# ProDoc_TeenAstro_Redux_v2_6_5M_2025-03-2.net
KiCad netlist of a schematic drawn in EasyEDA Pro
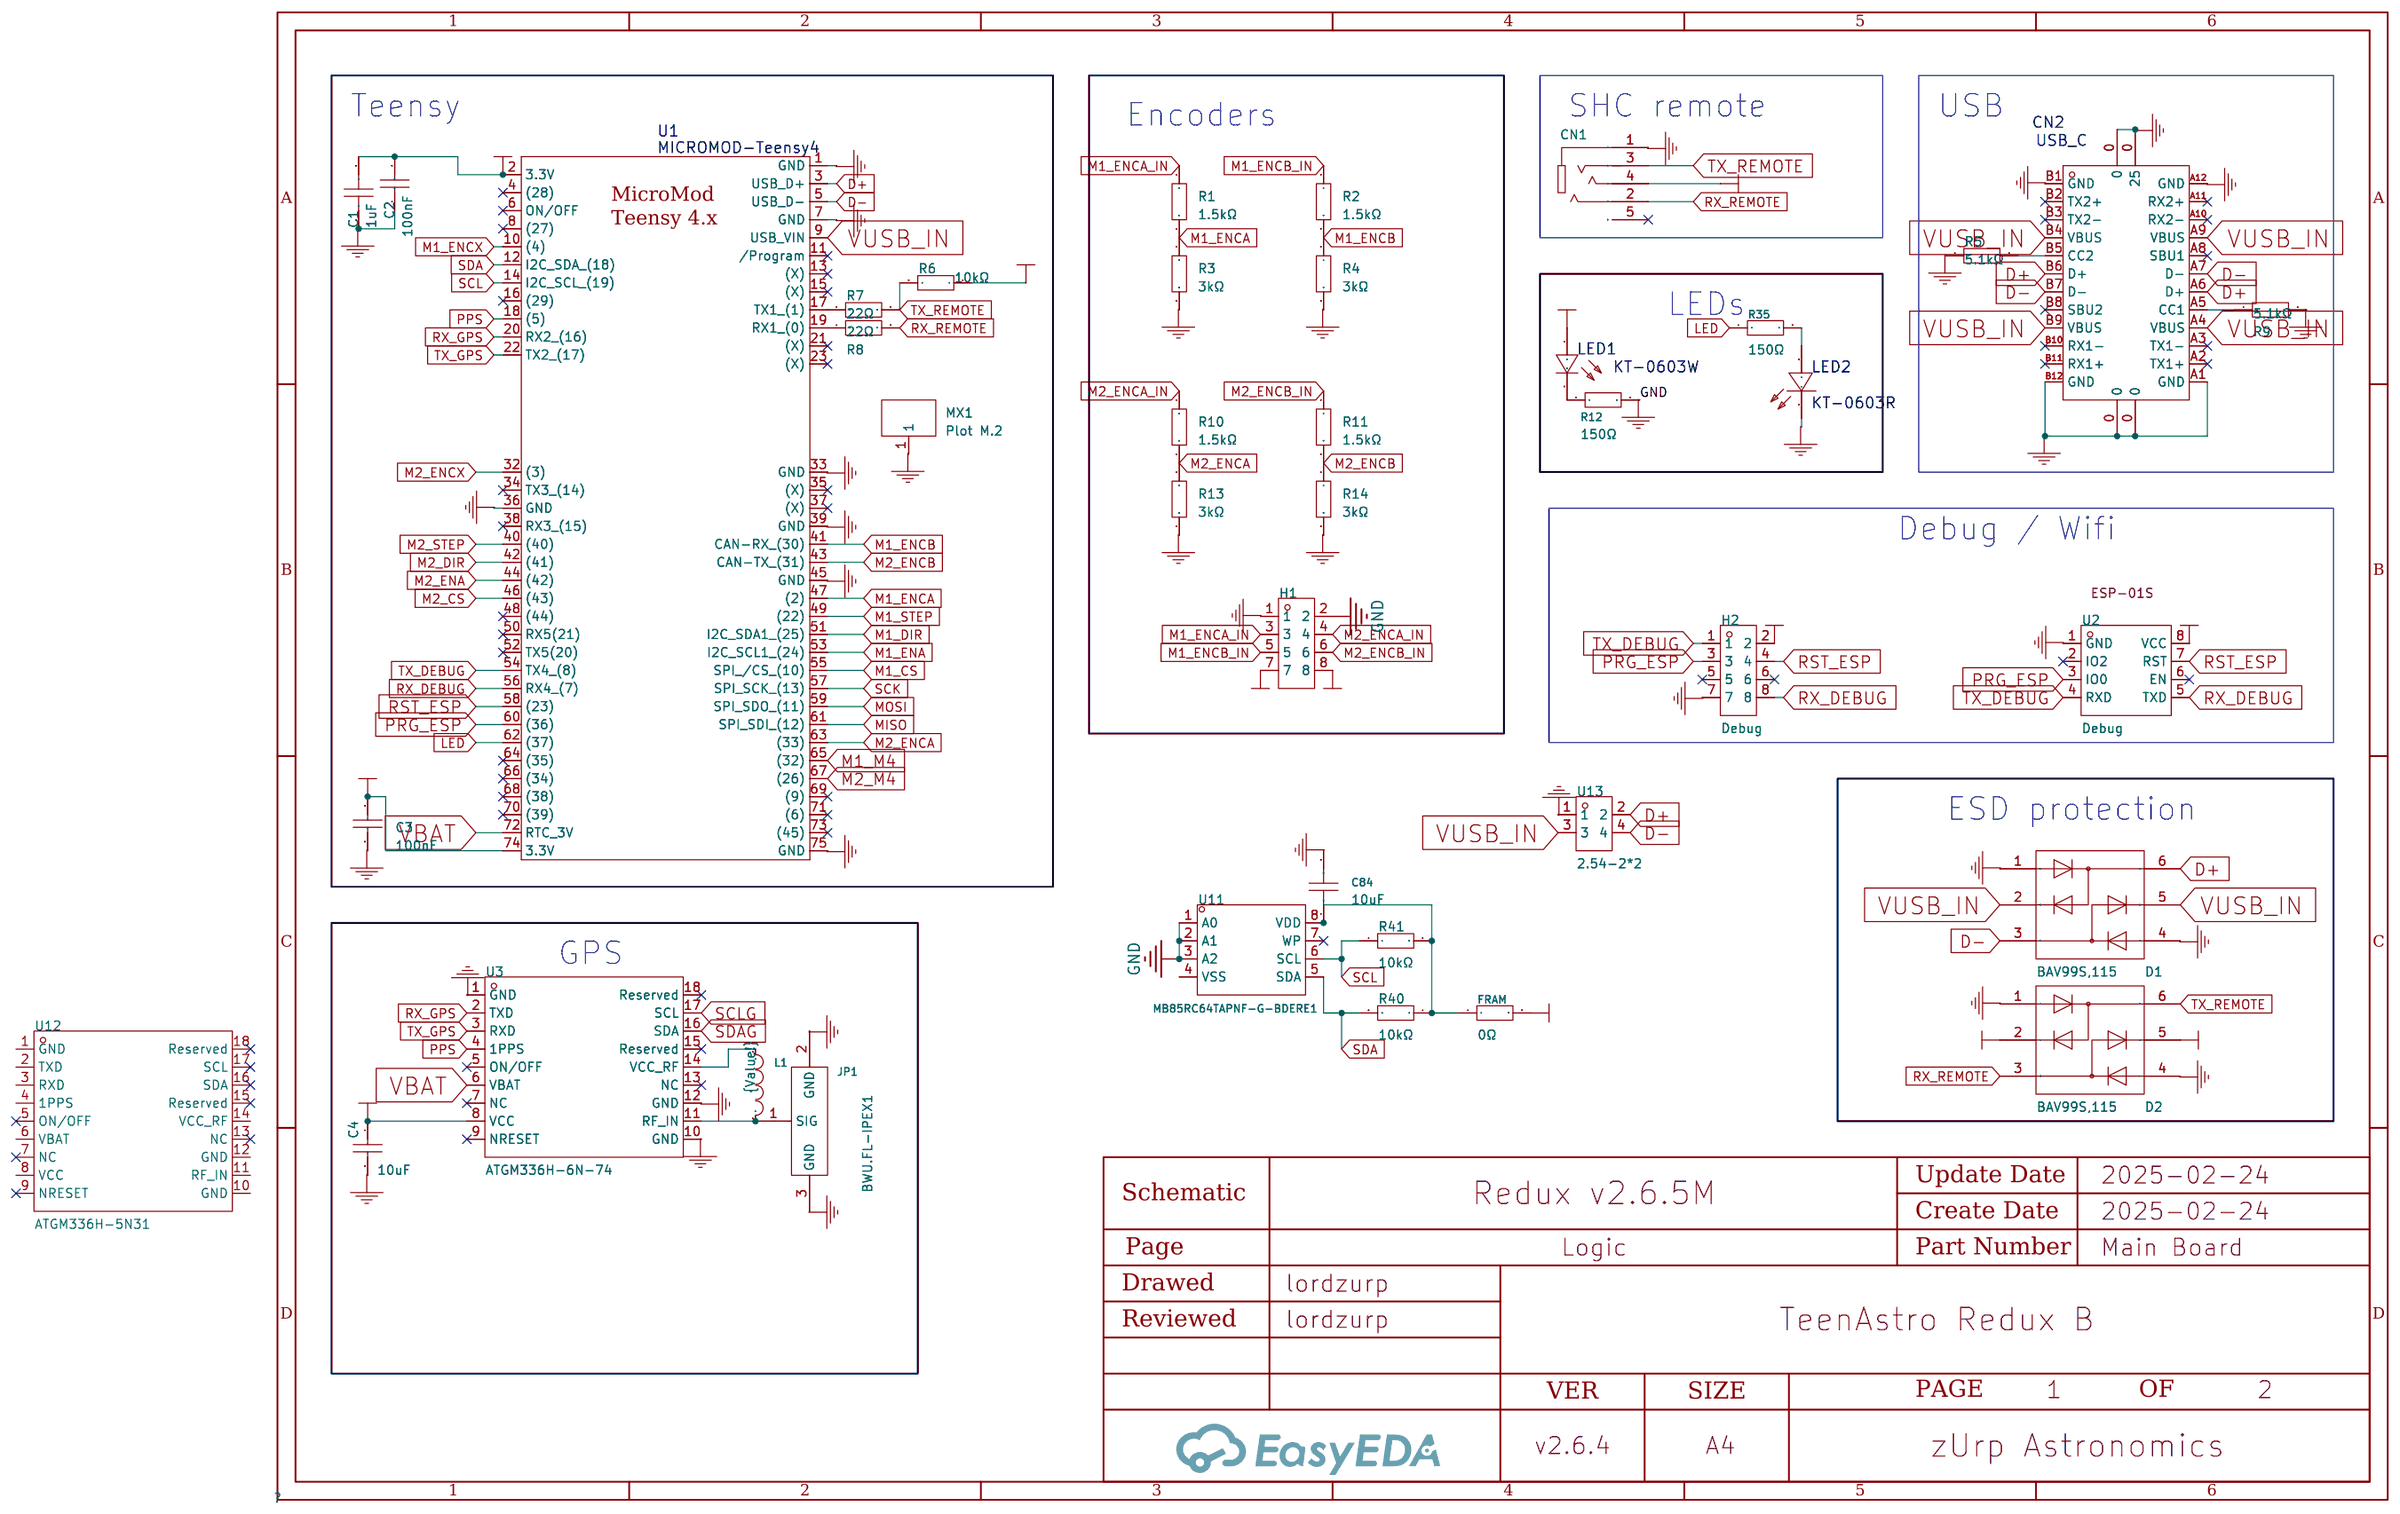
[diagram p0: Logic]
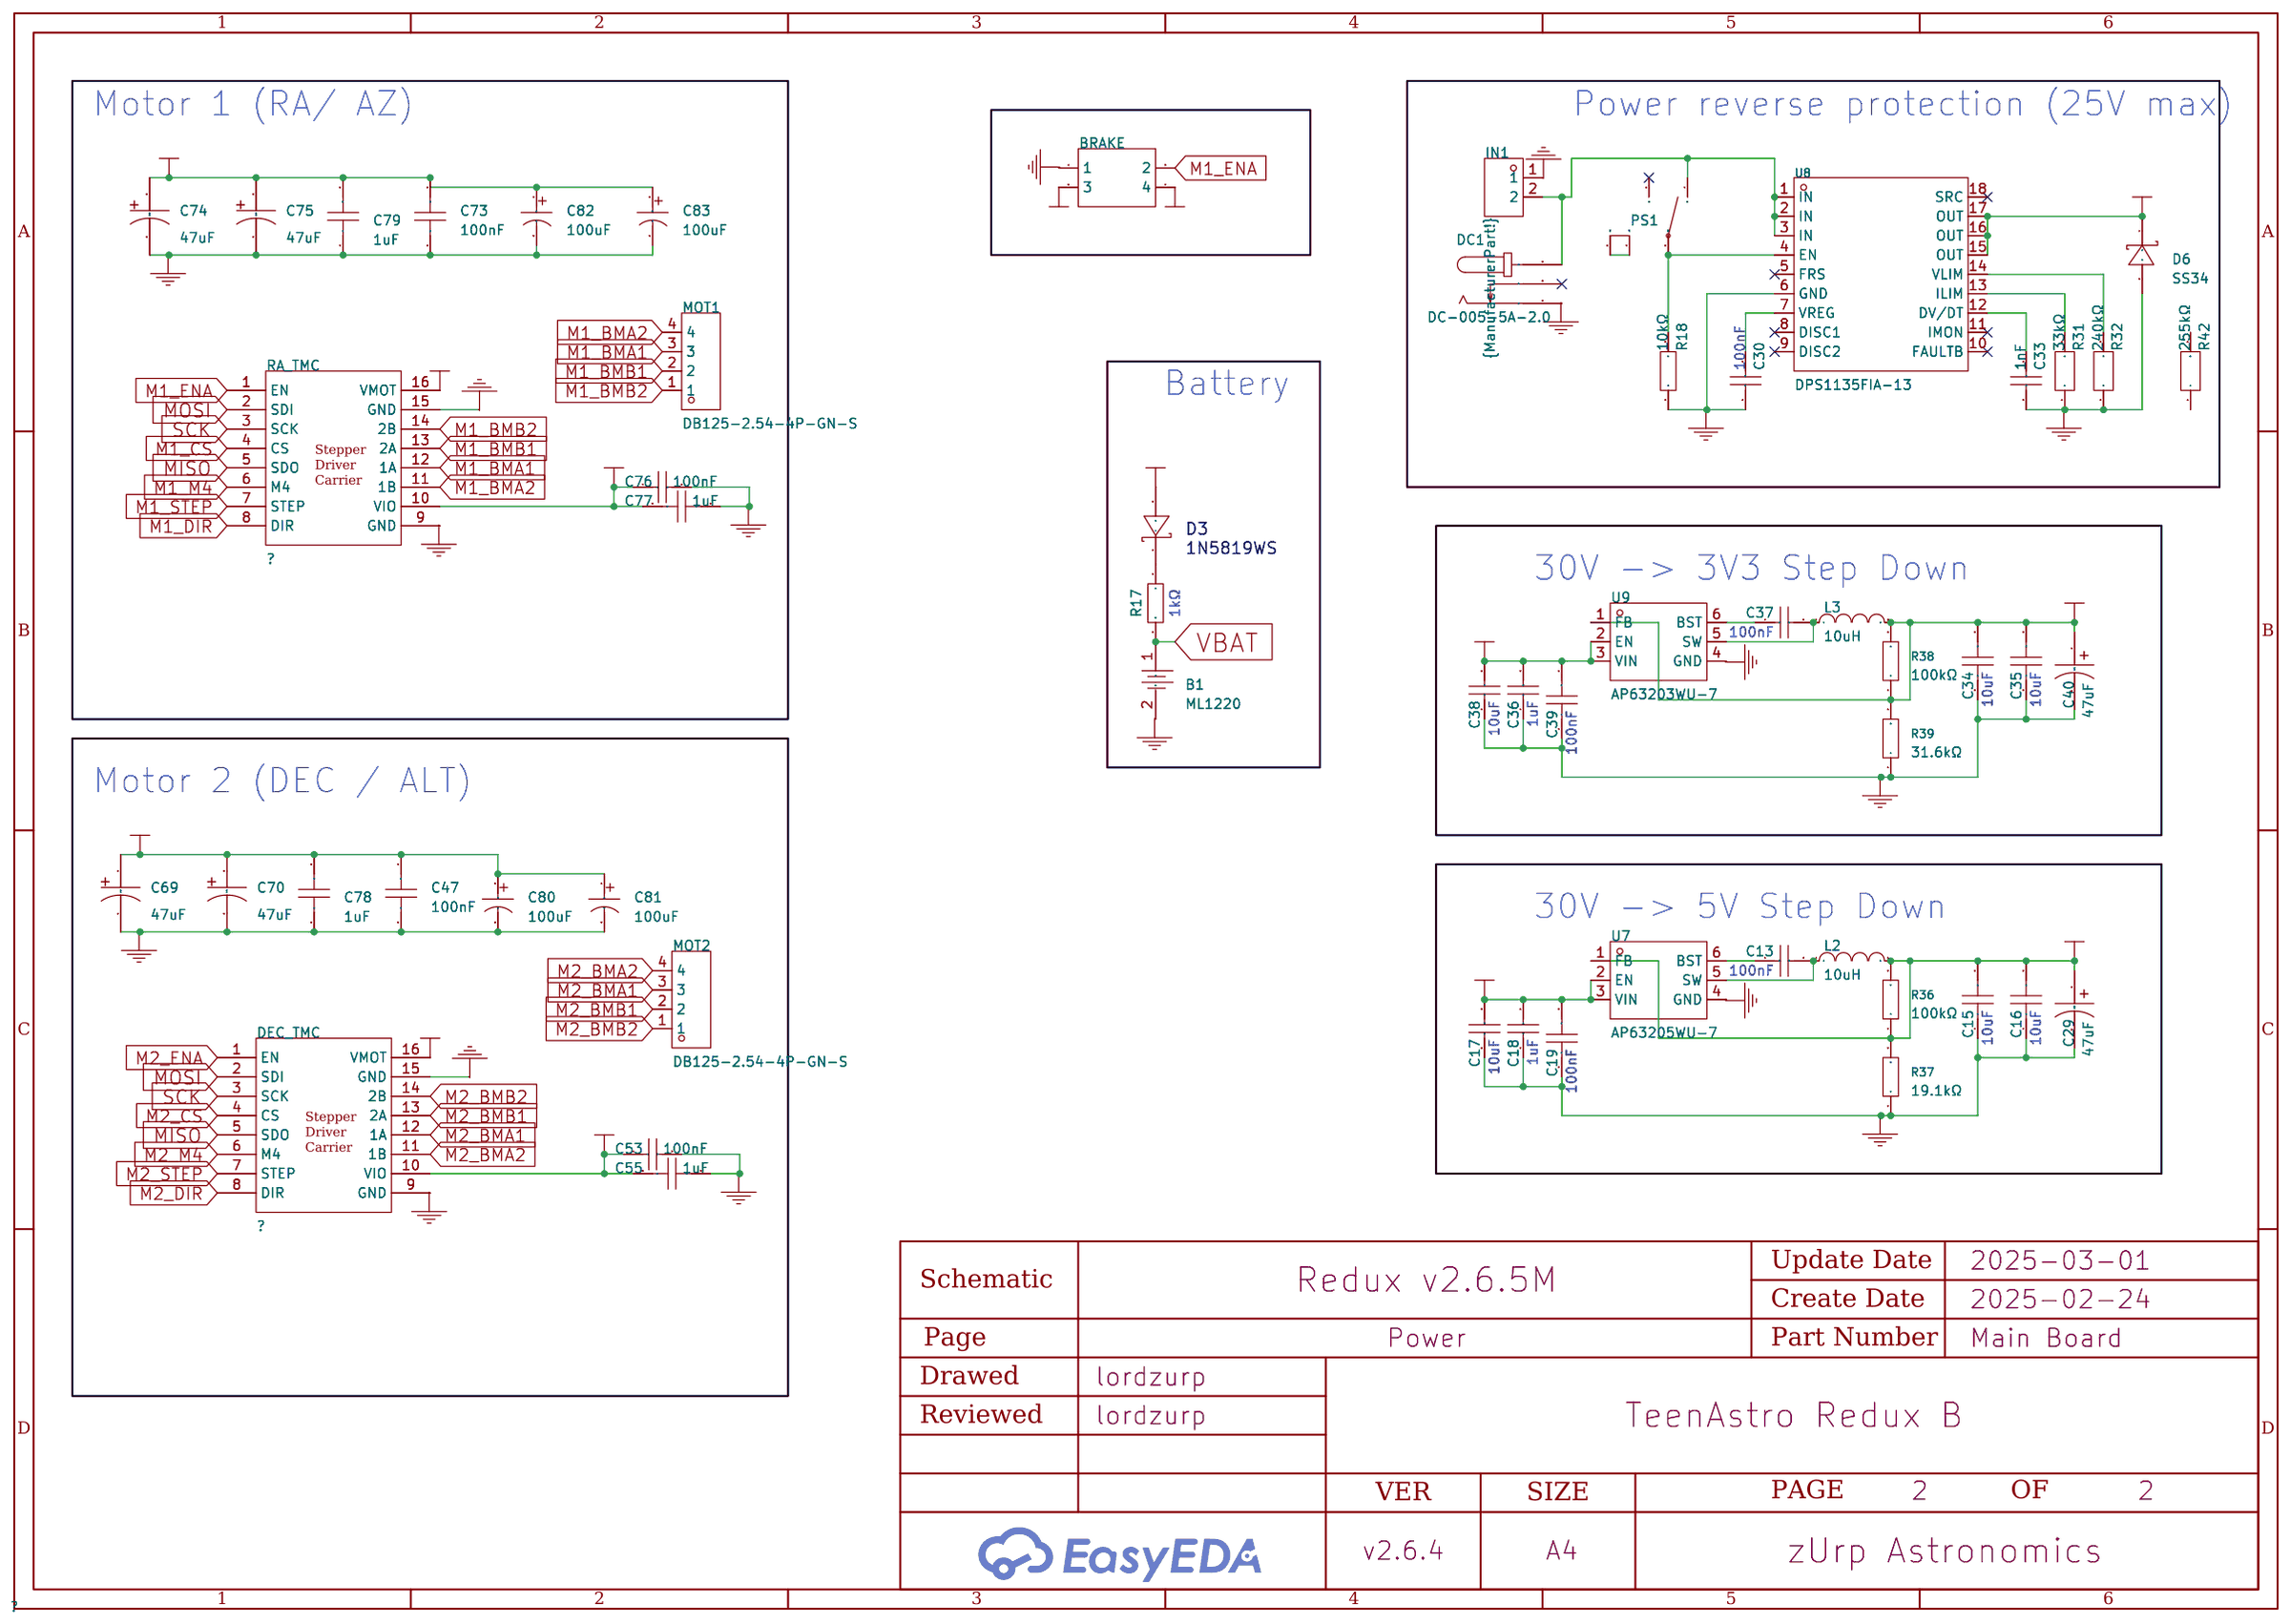
[diagram p1: Power]

(export (version "E")
  (design (tool "Eeschema 10.0.6"))
  (components
    (comp (ref "C1")
      (value "1uF")
      (footprint "easyedapro:C0402")
      (fields
        (field (name "Manufacturer Part") "CL05A105KA5NQNC")
        (field (name "Manufacturer") "SAMSUNG(三星)")
      )
      (libsource (lib "easyedapro") (part "CL05A105KA5NQNC"))
    )
    (comp (ref "C2")
      (value "100nF")
      (footprint "easyedapro:C0402")
      (fields
        (field (name "Manufacturer Part") "CL05B104KO5NNNC")
        (field (name "Manufacturer") "SAMSUNG(三星)")
      )
      (libsource (lib "easyedapro") (part "CL05B104KO5NNNC"))
    )
    (comp (ref "C3")
      (value "100nF")
      (footprint "easyedapro:C0402")
      (fields
        (field (name "Manufacturer Part") "CL05B104KO5NNNC")
        (field (name "Manufacturer") "SAMSUNG(三星)")
      )
      (libsource (lib "easyedapro") (part "CL05B104KO5NNNC"))
    )
    (comp (ref "C4")
      (value "10uF")
      (footprint "easyedapro:C1206")
      (fields
        (field (name "Manufacturer Part") "CL31A106KBHNNNE")
        (field (name "Manufacturer") "SAMSUNG(三星)")
      )
      (libsource (lib "easyedapro") (part "CL31A106KBHNNNE"))
    )
    (comp (ref "C84")
      (value "10uF")
      (footprint "easyedapro:C0603")
      (fields
        (field (name "Manufacturer Part") "CL10A106KP8NNNC")
        (field (name "Manufacturer") "SAMSUNG(三星)")
      )
      (libsource (lib "easyedapro") (part "CL10A106KP8NNNC"))
    )
    (comp (ref "CN1")
      (value "PJ-327E-SMT")
      (footprint "easyedapro:AUDIO-SMD_PJ-327E-SMT")
      (fields (field (name "Manufacturer") "XKBConnectivity(中国星坤)"))
      (libsource (lib "easyedapro") (part "PJ-327E-SMT"))
    )
    (comp (ref "CN2")
      (value "USB_C")
      (footprint "easyedapro:USB-C-SMD_TYPE-C-USB-18")
      (fields (field (name "Manufacturer Part") "105450-0101") (field (name "Manufacturer") "MOLEX"))
      (libsource (lib "easyedapro") (part "USB_C"))
    )
    (comp (ref "D1")
      (value "BAV99S,115")
      (footprint "easyedapro:SOT-363_L2.0-W1.3-P0.65-LS2.1-TL")
      (fields (field (name "Manufacturer") "Nexperia(安世)"))
      (libsource (lib "easyedapro") (part "BAV99S,135"))
    )
    (comp (ref "D2")
      (value "BAV99S,115")
      (footprint "easyedapro:SOT-363_L2.0-W1.3-P0.65-LS2.1-TL")
      (fields (field (name "Manufacturer") "Nexperia(安世)"))
      (libsource (lib "easyedapro") (part "BAV99S,135"))
    )
    (comp (ref "FRAM")
      (value "0Ω")
      (footprint "easyedapro:R0402")
      (fields
        (field (name "Manufacturer Part") "0402WGF0000TCE")
        (field (name "Manufacturer") "UNI-ROYAL(厚声)")
      )
      (libsource (lib "easyedapro") (part "0402WGF0000TCE"))
    )
    (comp (ref "H1")
      (value "DW127R-22-08-34")
      (fields (field (name "Manufacturer") "DEALON(德艺隆)"))
      (libsource (lib "easyedapro") (part "DZ254R-22-08-63"))
    )
    (comp (ref "H2")
      (value "Debug")
      (fields (field (name "Manufacturer Part") "DS1023-2*4SF11") (field (name "Manufacturer") "CONNFLY"))
      (libsource (lib "easyedapro") (part "DZ254R-22-08-63"))
    )
    (comp (ref "JP1")
      (value "BWU.FL-IPEX1")
      (fields (field (name "Manufacturer") "BAT WIRELESS(蝙蝠无线)"))
      (libsource (lib "easyedapro") (part "U.FL-R-SMT-1(80)"))
    )
    (comp (ref "L1")
      (value "{Value!}")
      (footprint "easyedapro:IND-SMD_L1.6-W0.8-1")
      (fields (field (name "Manufacturer Part") "LQW18AN47NJ00D") (field (name "Manufacturer") "muRata(村田)"))
      (libsource (lib "easyedapro") (part "LQW18AN47NJ00D"))
    )
    (comp (ref "LED1")
      (value "KT-0603W")
      (description "Emitted Color:White")
      (fields (field (name "Manufacturer") "KENTO"))
      (libsource (lib "easyedapro") (part "power"))
    )
    (comp (ref "LED2")
      (value "KT-0603R")
      (footprint "easyedapro:LED0603-RD")
      (fields (field (name "Manufacturer") "KENTO"))
      (libsource (lib "easyedapro") (part "KT-0603R"))
    )
    (comp (ref "MX1")
      (value "Plot M.2")
      (footprint "easyedapro:SMD_BD5.6-D4.1")
      (fields (field (name "Manufacturer Part") "SMTSO3030CTJ") (field (name "Manufacturer") "Sinhoo(雄和远景)"))
      (libsource (lib "easyedapro") (part "SMTSO3030CTJ"))
    )
    (comp (ref "R1")
      (value "1.5kΩ")
      (footprint "easyedapro:R0603")
      (fields
        (field (name "Manufacturer Part") "0603WAF1501T5E")
        (field (name "Manufacturer") "UNI-ROYAL(厚声)")
      )
      (libsource (lib "easyedapro") (part "0603WAF1501T5E"))
    )
    (comp (ref "R2")
      (value "1.5kΩ")
      (footprint "easyedapro:R0603")
      (fields
        (field (name "Manufacturer Part") "0603WAF1501T5E")
        (field (name "Manufacturer") "UNI-ROYAL(厚声)")
      )
      (libsource (lib "easyedapro") (part "0603WAF1501T5E"))
    )
    (comp (ref "R3")
      (value "3kΩ")
      (footprint "easyedapro:R0603")
      (fields
        (field (name "Manufacturer Part") "0603WAF3001T5E")
        (field (name "Manufacturer") "UNI-ROYAL(厚声)")
      )
      (libsource (lib "easyedapro") (part "0603WAF3001T5E"))
    )
    (comp (ref "R4")
      (value "3kΩ")
      (footprint "easyedapro:R0603")
      (fields
        (field (name "Manufacturer Part") "0603WAF3001T5E")
        (field (name "Manufacturer") "UNI-ROYAL(厚声)")
      )
      (libsource (lib "easyedapro") (part "0603WAF3001T5E"))
    )
    (comp (ref "R5")
      (value "5.1kΩ")
      (fields
        (field (name "Manufacturer Part") "0603WAF5101T5E")
        (field (name "Manufacturer") "UNI-ROYAL(厚声)")
      )
      (libsource (lib "easyedapro") (part "RC0603JR-075K1L"))
    )
    (comp (ref "R6")
      (value "10kΩ")
      (footprint "easyedapro:R0402")
      (fields
        (field (name "Manufacturer Part") "0402WGF1002TCE")
        (field (name "Manufacturer") "UNI-ROYAL(厚声)")
      )
      (libsource (lib "easyedapro") (part "0402WGF1002TCE"))
    )
    (comp (ref "R7")
      (value "22Ω")
      (footprint "easyedapro:R0402")
      (fields
        (field (name "Manufacturer Part") "0402WGF220JTCE")
        (field (name "Manufacturer") "UNI-ROYAL(厚声)")
      )
      (libsource (lib "easyedapro") (part "0402WGF220JTCE"))
    )
    (comp (ref "R8")
      (value "22Ω")
      (footprint "easyedapro:R0402")
      (fields
        (field (name "Manufacturer Part") "0402WGF220JTCE")
        (field (name "Manufacturer") "UNI-ROYAL(厚声)")
      )
      (libsource (lib "easyedapro") (part "0402WGF220JTCE"))
    )
    (comp (ref "R9")
      (value "5.1kΩ")
      (fields
        (field (name "Manufacturer Part") "0603WAF5101T5E")
        (field (name "Manufacturer") "UNI-ROYAL(厚声)")
      )
      (libsource (lib "easyedapro") (part "RC0603JR-075K1L"))
    )
    (comp (ref "R10")
      (value "1.5kΩ")
      (footprint "easyedapro:R0603")
      (fields
        (field (name "Manufacturer Part") "0603WAF1501T5E")
        (field (name "Manufacturer") "UNI-ROYAL(厚声)")
      )
      (libsource (lib "easyedapro") (part "0603WAF1501T5E"))
    )
    (comp (ref "R11")
      (value "1.5kΩ")
      (footprint "easyedapro:R0603")
      (fields
        (field (name "Manufacturer Part") "0603WAF1501T5E")
        (field (name "Manufacturer") "UNI-ROYAL(厚声)")
      )
      (libsource (lib "easyedapro") (part "0603WAF1501T5E"))
    )
    (comp (ref "R12") (value "150Ω") (libsource (lib "easyedapro") (part "0603WAF1001T5E")))
    (comp (ref "R13")
      (value "3kΩ")
      (footprint "easyedapro:R0603")
      (fields
        (field (name "Manufacturer Part") "0603WAF3001T5E")
        (field (name "Manufacturer") "UNI-ROYAL(厚声)")
      )
      (libsource (lib "easyedapro") (part "0603WAF3001T5E"))
    )
    (comp (ref "R14")
      (value "3kΩ")
      (footprint "easyedapro:R0603")
      (fields
        (field (name "Manufacturer Part") "0603WAF3001T5E")
        (field (name "Manufacturer") "UNI-ROYAL(厚声)")
      )
      (libsource (lib "easyedapro") (part "0603WAF3001T5E"))
    )
    (comp (ref "R35")
      (value "150Ω")
      (footprint "easyedapro:R0603")
      (fields
        (field (name "Manufacturer Part") "0603WAF1500T5E")
        (field (name "Manufacturer") "UNI-ROYAL(厚声)")
      )
      (libsource (lib "easyedapro") (part "0603WAF1500T5E"))
    )
    (comp (ref "R40")
      (value "10kΩ")
      (footprint "easyedapro:R0402")
      (fields
        (field (name "Manufacturer Part") "0402WGF1002TCE")
        (field (name "Manufacturer") "UNI-ROYAL(厚声)")
      )
      (libsource (lib "easyedapro") (part "0402WGF1002TCE"))
    )
    (comp (ref "R41")
      (value "10kΩ")
      (footprint "easyedapro:R0402")
      (fields
        (field (name "Manufacturer Part") "0402WGF1002TCE")
        (field (name "Manufacturer") "UNI-ROYAL(厚声)")
      )
      (libsource (lib "easyedapro") (part "0402WGF1002TCE"))
    )
    (comp (ref "U1")
      (value "MICROMOD-Teensy4")
      (footprint "easyedapro:M.2-CONNECTOR-E")
      (fields (field (name "Manufacturer") "Foxconn") (field (name "Manufacturer Part") "AS0BC21-S48BE-7H"))
      (libsource (lib "easyedapro") (part "MICROMOD-Teensy4"))
    )
    (comp (ref "U2")
      (value "2.4GHz")
      (footprint "easyedapro:WIFIM-TH_8P-L24.7-W14.4-P2.54")
      (fields (field (name "Manufacturer Part") "ESP-01S") (field (name "Manufacturer") "Ai-Thinker(安信可)"))
      (libsource (lib "easyedapro") (part "ESP-01"))
    )
    (comp (ref "U3")
      (value "ATGM336H-6N-74")
      (footprint "easyedapro:GPSM-SMD_ATGM336H-TR")
      (fields (field (name "Manufacturer") "杭州中科微"))
      (libsource (lib "easyedapro") (part "ATGM336H-5N31"))
    )
    (comp (ref "U11")
      (value "MB85RC64TAPNF-G-BDERE1")
      (footprint "easyedapro:SOP-8_L5.0-W4.0-P1.27-LS6.0-BL")
      (fields (field (name "Manufacturer") "RAMXEED/FUJITSU(富士通)"))
      (libsource (lib "easyedapro") (part "MB85RC64TAPNF-G-BDERE1"))
    )
    (comp (ref "U12")
      (value "ATGM336H-5N31")
      (footprint "easyedapro:GPSM-SMD_ATGM336H-TR")
      (fields (field (name "Manufacturer") "杭州中科微"))
      (libsource (lib "easyedapro") (part "ATGM336H-5N31"))
    )
    (comp (ref "U13")
      (value "2.54-2*2")
      (footprint "easyedapro:HDR-TH_4P-P2.54-V-F-R2-C2-S2.54")
      (fields (field (name "Manufacturer") "ZHOURI(洲日)"))
      (libsource (lib "easyedapro") (part "2.54-2*2"))
    )
    (comp (ref "B1")
      (value "ML1220")
      (footprint "easyedapro:BAT-SMD_CR1220-2")
      (fields (field (name "Manufacturer Part") "CR1220-2") (field (name "Manufacturer") "Q&J"))
      (libsource (lib "easyedapro") (part "CR1220-2"))
    )
    (comp (ref "BRAKE")
      (value "X4621WVS-2x02I-C40D64")
      (fields (field (name "Manufacturer") "XKB Connection(中国星坤)"))
      (libsource (lib "easyedapro") (part "Header-Male-2.54_2x2"))
    )
    (comp (ref "C13")
      (value "100nF")
      (footprint "easyedapro:C0402")
      (fields
        (field (name "Manufacturer Part") "CL05B104KO5NNNC")
        (field (name "Manufacturer") "SAMSUNG(三星)")
      )
      (libsource (lib "easyedapro") (part "CL05B104KO5NNNC"))
    )
    (comp (ref "C15")
      (value "10uF")
      (fields
        (field (name "Manufacturer Part") "CL21A106KAYNNNE")
        (field (name "Manufacturer") "SAMSUNG(三星)")
      )
      (libsource (lib "easyedapro") (part "C3225X5R1E226MT000E"))
    )
    (comp (ref "C16")
      (value "10uF")
      (fields
        (field (name "Manufacturer Part") "CL21A106KAYNNNE")
        (field (name "Manufacturer") "SAMSUNG(三星)")
      )
      (libsource (lib "easyedapro") (part "C3225X5R1E226MT000E"))
    )
    (comp (ref "C17")
      (value "10uF")
      (footprint "easyedapro:C1206")
      (fields
        (field (name "Manufacturer Part") "CL31A106KBHNNNE")
        (field (name "Manufacturer") "SAMSUNG(三星)")
      )
      (libsource (lib "easyedapro") (part "CL31A106KBHNNNE"))
    )
    (comp (ref "C18")
      (value "1uF")
      (footprint "easyedapro:C0805")
      (fields
        (field (name "Manufacturer Part") "CL21B105KBFNNNE")
        (field (name "Manufacturer") "SAMSUNG(三星)")
      )
      (libsource (lib "easyedapro") (part "CL21B105KBFNNNE"))
    )
    (comp (ref "C19")
      (value "100nF")
      (footprint "easyedapro:C0603")
      (fields
        (field (name "Manufacturer Part") "CC0603KRX7R9BB104")
        (field (name "Manufacturer") "YAGEO(国巨)")
      )
      (libsource (lib "easyedapro") (part "CC0603KRX7R9BB104"))
    )
    (comp (ref "C29")
      (value "47uF")
      (fields
        (field (name "Manufacturer Part") "CA45-A-10V-47uF-M")
        (field (name "Manufacturer") "CEC(振华新云)")
      )
      (libsource (lib "easyedapro") (part "F930J476MAA_C471392"))
    )
    (comp (ref "C30")
      (value "100nF")
      (footprint "easyedapro:C0402")
      (fields
        (field (name "Manufacturer Part") "CL05B104KO5NNNC")
        (field (name "Manufacturer") "SAMSUNG(三星)")
      )
      (libsource (lib "easyedapro") (part "CL05B104KO5NNNC"))
    )
    (comp (ref "C33")
      (value "1nF")
      (footprint "easyedapro:C0402")
      (fields (field (name "Manufacturer Part") "0402B102K500NT") (field (name "Manufacturer") "FH(风华)"))
      (libsource (lib "easyedapro") (part "0402B102K500NT"))
    )
    (comp (ref "C34")
      (value "10uF")
      (fields
        (field (name "Manufacturer Part") "CL21A106KAYNNNE")
        (field (name "Manufacturer") "SAMSUNG(三星)")
      )
      (libsource (lib "easyedapro") (part "C3225X5R1E226MT000E"))
    )
    (comp (ref "C35")
      (value "10uF")
      (fields
        (field (name "Manufacturer Part") "CL21A106KAYNNNE")
        (field (name "Manufacturer") "SAMSUNG(三星)")
      )
      (libsource (lib "easyedapro") (part "C3225X5R1E226MT000E"))
    )
    (comp (ref "C36")
      (value "1uF")
      (footprint "easyedapro:C0805")
      (fields
        (field (name "Manufacturer Part") "CL21B105KBFNNNE")
        (field (name "Manufacturer") "SAMSUNG(三星)")
      )
      (libsource (lib "easyedapro") (part "CL21B105KBFNNNE"))
    )
    (comp (ref "C37")
      (value "100nF")
      (footprint "easyedapro:C0402")
      (fields
        (field (name "Manufacturer Part") "CL05B104KO5NNNC")
        (field (name "Manufacturer") "SAMSUNG(三星)")
      )
      (libsource (lib "easyedapro") (part "CL05B104KO5NNNC"))
    )
    (comp (ref "C38")
      (value "10uF")
      (footprint "easyedapro:C1206")
      (fields
        (field (name "Manufacturer Part") "CL31A106KBHNNNE")
        (field (name "Manufacturer") "SAMSUNG(三星)")
      )
      (libsource (lib "easyedapro") (part "CL31A106KBHNNNE"))
    )
    (comp (ref "C39")
      (value "100nF")
      (footprint "easyedapro:C0603")
      (fields
        (field (name "Manufacturer Part") "CC0603KRX7R9BB104")
        (field (name "Manufacturer") "YAGEO(国巨)")
      )
      (libsource (lib "easyedapro") (part "CC0603KRX7R9BB104"))
    )
    (comp (ref "C40")
      (value "47uF")
      (fields
        (field (name "Manufacturer Part") "CA45-A-10V-47uF-M")
        (field (name "Manufacturer") "CEC(振华新云)")
      )
      (libsource (lib "easyedapro") (part "F930J476MAA_C471392"))
    )
    (comp (ref "C47")
      (value "100nF")
      (footprint "easyedapro:C0603")
      (fields
        (field (name "Manufacturer Part") "CC0603KRX7R9BB104")
        (field (name "Manufacturer") "YAGEO(国巨)")
      )
      (libsource (lib "easyedapro") (part "CC0603KRX7R9BB104"))
    )
    (comp (ref "C53")
      (value "100nF")
      (footprint "easyedapro:C0402")
      (fields
        (field (name "Manufacturer Part") "CL05B104KO5NNNC")
        (field (name "Manufacturer") "SAMSUNG(三星)")
      )
      (libsource (lib "easyedapro") (part "CL05B104KO5NNNC"))
    )
    (comp (ref "C55")
      (value "1uF")
      (footprint "easyedapro:C0402")
      (fields
        (field (name "Manufacturer Part") "CL05A105KA5NQNC")
        (field (name "Manufacturer") "SAMSUNG(三星)")
      )
      (libsource (lib "easyedapro") (part "CL05A105KA5NQNC"))
    )
    (comp (ref "C69")
      (value "47uF")
      (footprint "easyedapro:CAP-SMD_BD5.0-L5.3-W5.3-FD")
      (fields (field (name "Manufacturer Part") "EEEFT1V470AR") (field (name "Manufacturer") "PANASONIC(松下)"))
      (libsource (lib "easyedapro") (part "EEE-FT1V470AR"))
    )
    (comp (ref "C70")
      (value "47uF")
      (footprint "easyedapro:CAP-SMD_BD5.0-L5.3-W5.3-FD")
      (fields (field (name "Manufacturer Part") "EEEFT1V470AR") (field (name "Manufacturer") "PANASONIC(松下)"))
      (libsource (lib "easyedapro") (part "EEE-FT1V470AR"))
    )
    (comp (ref "C73")
      (value "100nF")
      (footprint "easyedapro:C0603")
      (fields
        (field (name "Manufacturer Part") "CC0603KRX7R9BB104")
        (field (name "Manufacturer") "YAGEO(国巨)")
      )
      (libsource (lib "easyedapro") (part "CC0603KRX7R9BB104"))
    )
    (comp (ref "C74")
      (value "47uF")
      (footprint "easyedapro:CAP-SMD_BD5.0-L5.3-W5.3-FD")
      (fields (field (name "Manufacturer Part") "EEEFT1V470AR") (field (name "Manufacturer") "PANASONIC(松下)"))
      (libsource (lib "easyedapro") (part "EEE-FT1V470AR"))
    )
    (comp (ref "C75")
      (value "47uF")
      (footprint "easyedapro:CAP-SMD_BD5.0-L5.3-W5.3-FD")
      (fields (field (name "Manufacturer Part") "EEEFT1V470AR") (field (name "Manufacturer") "PANASONIC(松下)"))
      (libsource (lib "easyedapro") (part "EEE-FT1V470AR"))
    )
    (comp (ref "C76")
      (value "100nF")
      (footprint "easyedapro:C0402")
      (fields
        (field (name "Manufacturer Part") "CL05B104KO5NNNC")
        (field (name "Manufacturer") "SAMSUNG(三星)")
      )
      (libsource (lib "easyedapro") (part "CL05B104KO5NNNC"))
    )
    (comp (ref "C77")
      (value "1uF")
      (footprint "easyedapro:C0402")
      (fields
        (field (name "Manufacturer Part") "CL05A105KA5NQNC")
        (field (name "Manufacturer") "SAMSUNG(三星)")
      )
      (libsource (lib "easyedapro") (part "CL05A105KA5NQNC"))
    )
    (comp (ref "C78")
      (value "1uF")
      (footprint "easyedapro:C0603")
      (fields
        (field (name "Manufacturer Part") "CGA0603X5R105K350JT")
        (field (name "Manufacturer") "HRE(芯声)")
      )
      (libsource (lib "easyedapro") (part "CGA0603X5R105K350JT"))
    )
    (comp (ref "C79")
      (value "1uF")
      (footprint "easyedapro:C0603")
      (fields
        (field (name "Manufacturer Part") "CGA0603X5R105K350JT")
        (field (name "Manufacturer") "HRE(芯声)")
      )
      (libsource (lib "easyedapro") (part "CGA0603X5R105K350JT"))
    )
    (comp (ref "C80")
      (value "100uF")
      (footprint "easyedapro:CAP-TH_BD5.0-P2.00-D0.8-FD")
      (fields
        (field (name "Manufacturer Part") "KM107M025D11RR0VH2FP0")
        (field (name "Manufacturer") "CX(承兴)")
      )
      (libsource (lib "easyedapro") (part "100uF 25V 5*11"))
    )
    (comp (ref "C81")
      (value "100uF")
      (footprint "easyedapro:CAP-TH_BD5.0-P2.00-D0.8-FD")
      (fields
        (field (name "Manufacturer Part") "KM107M025D11RR0VH2FP0")
        (field (name "Manufacturer") "CX(承兴)")
      )
      (libsource (lib "easyedapro") (part "100uF 25V 5*11"))
    )
    (comp (ref "C82")
      (value "100uF")
      (footprint "easyedapro:CAP-TH_BD5.0-P2.00-D0.8-FD")
      (fields
        (field (name "Manufacturer Part") "KM107M025D11RR0VH2FP0")
        (field (name "Manufacturer") "CX(承兴)")
      )
      (libsource (lib "easyedapro") (part "100uF 25V 5*11"))
    )
    (comp (ref "C83")
      (value "100uF")
      (footprint "easyedapro:CAP-TH_BD5.0-P2.00-D0.8-FD")
      (fields
        (field (name "Manufacturer Part") "KM107M025D11RR0VH2FP0")
        (field (name "Manufacturer") "CX(承兴)")
      )
      (libsource (lib "easyedapro") (part "100uF 25V 5*11"))
    )
    (comp (ref "D3")
      (value "1N5819WS")
      (description "Forward Voltage (Vf@If):600mV@1A Reverse Voltage (Vr):40V Average Rectified Current (Io):1A")
      (fields (field (name "Manufacturer") "Hottech(合科泰)"))
      (libsource (lib "easyedapro") (part "RB751V40T1G"))
    )
    (comp (ref "D6")
      (value "SS34")
      (footprint "easyedapro:SMA_L4.3-W2.6-LS5.2-RD")
      (fields (field (name "Manufacturer") "MDD(辰达半导体)"))
      (libsource (lib "easyedapro") (part "SS34_C8678"))
    )
    (comp (ref "DC1")
      (value "DC-005-5A-2.0")
      (fields (field (name "Manufacturer") "XKB Connection(中国星坤)"))
      (libsource (lib "easyedapro") (part "DC005-2.5MM"))
    )
    (comp (ref "DEC_TMC")
      (value "?")
      (footprint "easyedapro:TMC2130 STEPPER MOTOR DRIVER CARRIER")
      (libsource (lib "easyedapro") (part "TMC2130 Stepper Motor Driver Carrier"))
    )
    (comp (ref "IN1")
      (value "{ManufacturerPart!}")
      (footprint "easyedapro:HDR-TH_2P-P2.54-V-M")
      (fields (field (name "Manufacturer Part") "HEAD2"))
      (libsource (lib "easyedapro") (part "HEAD2"))
    )
    (comp (ref "L2")
      (value "10uH")
      (fields
        (field (name "Manufacturer Part") "SWPA252012S100MT")
        (field (name "Manufacturer") "Sunlord(顺络)")
      )
      (libsource (lib "easyedapro") (part "1277AS-H-4R7M=P2"))
    )
    (comp (ref "L3")
      (value "10uH")
      (fields
        (field (name "Manufacturer Part") "SWPA252012S100MT")
        (field (name "Manufacturer") "Sunlord(顺络)")
      )
      (libsource (lib "easyedapro") (part "1277AS-H-4R7M=P2"))
    )
    (comp (ref "MOT1")
      (value "DB125-2.54-4P-GN-S")
      (fields (field (name "Manufacturer") "DORABO(地博电气)"))
      (libsource (lib "easyedapro") (part "DB125-3.5-4P-GN"))
    )
    (comp (ref "MOT2")
      (value "DB125-2.54-4P-GN-S")
      (fields (field (name "Manufacturer") "DORABO(地博电气)"))
      (libsource (lib "easyedapro") (part "DB125-3.5-4P-GN"))
    )
    (comp (ref "PS1")
      (value "~")
      (footprint "easyedapro:Power_switch")
      (description "farnell 1550227\n4US1R102M7RN")
      (fields (field (name "Manufacturer Part") "4US1R102M7RN") (field (name "Manufacturer") "MULTICOMP PRO"))
      (libsource (lib "easyedapro") (part "Power_Switch"))
    )
    (comp (ref "R17") (value "1kΩ") (libsource (lib "easyedapro") (part "0603WAF1001T5E")))
    (comp (ref "R18")
      (value "10kΩ")
      (footprint "easyedapro:R0402")
      (fields
        (field (name "Manufacturer Part") "0402WGF1002TCE")
        (field (name "Manufacturer") "UNI-ROYAL(厚声)")
      )
      (libsource (lib "easyedapro") (part "0402WGF1002TCE"))
    )
    (comp (ref "R31")
      (value "33kΩ")
      (fields
        (field (name "Manufacturer Part") "0603WAF3302T5E")
        (field (name "Manufacturer") "UNI-ROYAL(厚声)")
      )
      (libsource (lib "easyedapro") (part "RT0603BRD0740KL"))
    )
    (comp (ref "R32")
      (value "240kΩ")
      (fields
        (field (name "Manufacturer Part") "0603WAF2403T5E")
        (field (name "Manufacturer") "UNI-ROYAL(厚声)")
      )
      (libsource (lib "easyedapro") (part "AR03BTCX2703"))
    )
    (comp (ref "R36")
      (value "100kΩ")
      (footprint "easyedapro:R0402")
      (fields
        (field (name "Manufacturer Part") "0402WGF1003TCE")
        (field (name "Manufacturer") "UNI-ROYAL(厚声)")
      )
      (libsource (lib "easyedapro") (part "0402WGF1003TCE"))
    )
    (comp (ref "R37")
      (value "19.1kΩ")
      (footprint "easyedapro:R0603")
      (fields
        (field (name "Manufacturer Part") "0603WAF1912T5E")
        (field (name "Manufacturer") "UNI-ROYAL(厚声)")
      )
      (libsource (lib "easyedapro") (part "0603WAF1912T5E"))
    )
    (comp (ref "R38")
      (value "100kΩ")
      (footprint "easyedapro:R0402")
      (fields
        (field (name "Manufacturer Part") "0402WGF1003TCE")
        (field (name "Manufacturer") "UNI-ROYAL(厚声)")
      )
      (libsource (lib "easyedapro") (part "0402WGF1003TCE"))
    )
    (comp (ref "R39")
      (value "31.6kΩ")
      (footprint "easyedapro:R0603")
      (fields
        (field (name "Manufacturer Part") "0603WAF3162T5E")
        (field (name "Manufacturer") "UNI-ROYAL(厚声)")
      )
      (libsource (lib "easyedapro") (part "0603WAF3162T5E"))
    )
    (comp (ref "R42")
      (value "255kΩ")
      (fields (field (name "Manufacturer Part") "RC0603FR-07255KL") (field (name "Manufacturer") "YAGEO(国巨)"))
      (libsource (lib "easyedapro") (part "AR03BTCX2703"))
    )
    (comp (ref "RA_TMC")
      (value "?")
      (footprint "easyedapro:TMC2130 STEPPER MOTOR DRIVER CARRIER")
      (libsource (lib "easyedapro") (part "TMC2130 Stepper Motor Driver Carrier"))
    )
    (comp (ref "U7")
      (value "AP63205WU-7")
      (footprint "easyedapro:TSOT-23-6_L2.9-W1.6-P0.95-LS2.8-BL")
      (fields (field (name "Manufacturer") "DIODES(美台)"))
      (libsource (lib "easyedapro") (part "AP63205WU-7"))
    )
    (comp (ref "U8")
      (value "DPS1135FIA-13")
      (footprint "easyedapro:QFN-17_L4.0-W4.0-P0.50-TL-EP")
      (fields (field (name "Manufacturer") "DIODES(美台)"))
      (libsource (lib "easyedapro") (part "DPS1135FIA-13"))
    )
    (comp (ref "U9")
      (value "AP63203WU-7")
      (footprint "easyedapro:TSOT-23-6_L2.9-W1.6-P0.95-LS2.8-BL")
      (fields (field (name "Manufacturer") "DIODES(美台)"))
      (libsource (lib "easyedapro") (part "AP63205WU-7"))
    )
  )
  (nets
    (net (code "1") (name "+3.3V") (class "Default")
      (node (ref "BRAKE") (pin "4") (pinfunction "4_4") (pintype "input"))
      (node (ref "C1") (pin "2") (pinfunction "2_2") (pintype "unspecified"))
      (node (ref "C2") (pin "2") (pinfunction "2_2") (pintype "input"))
      (node (ref "C3") (pin "1") (pinfunction "1_1") (pintype "input"))
      (node (ref "C34") (pin "2") (pinfunction "2_2") (pintype "input"))
      (node (ref "C35") (pin "2") (pinfunction "2_2") (pintype "input"))
      (node (ref "C4") (pin "1") (pinfunction "1_1") (pintype "input"))
      (node (ref "C40") (pin "1") (pinfunction "1_1") (pintype "unspecified"))
      (node (ref "C53") (pin "1") (pinfunction "1_1") (pintype "input"))
      (node (ref "C55") (pin "2") (pinfunction "2_2") (pintype "unspecified"))
      (node (ref "C76") (pin "1") (pinfunction "1_1") (pintype "input"))
      (node (ref "C77") (pin "2") (pinfunction "2_2") (pintype "unspecified"))
      (node (ref "D2") (pin "2") (pinfunction "C_2") (pintype "input"))
      (node (ref "D2") (pin "5") (pinfunction "C_5") (pintype "input"))
      (node (ref "D3") (pin "2") (pinfunction "A_2") (pintype "input"))
      (node (ref "DEC_TMC") (pin "10") (pinfunction "VIO_10") (pintype "input"))
      (node (ref "FRAM") (pin "2") (pinfunction "2_2") (pintype "input"))
      (node (ref "H2") (pin "2") (pinfunction "2_2") (pintype "input"))
      (node (ref "L3") (pin "2") (pinfunction "2_2") (pintype "input"))
      (node (ref "LED1") (pin "1") (pinfunction "A_1") (pintype "input"))
      (node (ref "R38") (pin "1") (pinfunction "1_1") (pintype "input"))
      (node (ref "R38") (pin "2") (pinfunction "2_2") (pintype "input"))
      (node (ref "R39") (pin "2") (pinfunction "2_2") (pintype "input"))
      (node (ref "R6") (pin "1") (pinfunction "1_1") (pintype "input"))
      (node (ref "RA_TMC") (pin "10") (pinfunction "VIO_10") (pintype "input"))
      (node (ref "U1") (pin "2") (pinfunction "3.3V_2") (pintype "input"))
      (node (ref "U1") (pin "74") (pinfunction "3.3V_74") (pintype "input"))
      (node (ref "U2") (pin "8") (pinfunction "VCC_8") (pintype "input"))
      (node (ref "U3") (pin "8") (pinfunction "VCC_8") (pintype "input"))
      (node (ref "U9") (pin "1") (pinfunction "FB_1") (pintype "input"))
    )
    (net (code "2") (name "+5V") (class "Default")
      (node (ref "C15") (pin "2") (pinfunction "2_2") (pintype "input"))
      (node (ref "C16") (pin "2") (pinfunction "2_2") (pintype "input"))
      (node (ref "C29") (pin "1") (pinfunction "1_1") (pintype "unspecified"))
      (node (ref "CN1") (pin "4") (pinfunction "4_4") (pintype "input"))
      (node (ref "H1") (pin "7") (pinfunction "7_7") (pintype "input"))
      (node (ref "H1") (pin "8") (pinfunction "8_8") (pintype "input"))
      (node (ref "L2") (pin "2") (pinfunction "2_2") (pintype "input"))
      (node (ref "R36") (pin "1") (pinfunction "1_1") (pintype "input"))
      (node (ref "R36") (pin "2") (pinfunction "2_2") (pintype "input"))
      (node (ref "R37") (pin "2") (pinfunction "2_2") (pintype "input"))
      (node (ref "U7") (pin "1") (pinfunction "FB_1") (pintype "input"))
    )
    (net (code "3") (name "D+") (class "Default")
      (node (ref "CN2") (pin "A6") (pinfunction "D+_A6") (pintype "input"))
      (node (ref "CN2") (pin "B6") (pinfunction "D+_B6") (pintype "input"))
      (node (ref "D1") (pin "6") (pinfunction "AC_6") (pintype "input"))
      (node (ref "U1") (pin "3") (pinfunction "USB_D+_3") (pintype "bidirectional"))
      (node (ref "U13") (pin "2") (pinfunction "2_2") (pintype "unspecified"))
    )
    (net (code "4") (name "D-") (class "Default")
      (node (ref "CN2") (pin "A7") (pinfunction "D-_A7") (pintype "input"))
      (node (ref "CN2") (pin "B7") (pinfunction "D-_B7") (pintype "input"))
      (node (ref "D1") (pin "3") (pinfunction "AC_3") (pintype "input"))
      (node (ref "U1") (pin "5") (pinfunction "USB_D-_5") (pintype "bidirectional"))
      (node (ref "U13") (pin "4") (pinfunction "4_4") (pintype "unspecified"))
    )
    (net (code "5") (name "GND") (class "Default")
      (node (ref "B1") (pin "2") (pinfunction "2_2") (pintype "input"))
      (node (ref "BRAKE") (pin "1") (pinfunction "1_1") (pintype "input"))
      (node (ref "C1") (pin "1") (pinfunction "1_1") (pintype "unspecified"))
      (node (ref "C15") (pin "1") (pinfunction "1_1") (pintype "input"))
      (node (ref "C16") (pin "1") (pinfunction "1_1") (pintype "input"))
      (node (ref "C17") (pin "1") (pinfunction "1_1") (pintype "input"))
      (node (ref "C18") (pin "1") (pinfunction "1_1") (pintype "input"))
      (node (ref "C19") (pin "1") (pinfunction "1_1") (pintype "input"))
      (node (ref "C2") (pin "1") (pinfunction "1_1") (pintype "input"))
      (node (ref "C29") (pin "2") (pinfunction "2_2") (pintype "unspecified"))
      (node (ref "C3") (pin "2") (pinfunction "2_2") (pintype "input"))
      (node (ref "C30") (pin "1") (pinfunction "1_1") (pintype "input"))
      (node (ref "C33") (pin "2") (pinfunction "2_2") (pintype "input"))
      (node (ref "C34") (pin "1") (pinfunction "1_1") (pintype "input"))
      (node (ref "C35") (pin "1") (pinfunction "1_1") (pintype "input"))
      (node (ref "C36") (pin "1") (pinfunction "1_1") (pintype "input"))
      (node (ref "C38") (pin "1") (pinfunction "1_1") (pintype "input"))
      (node (ref "C39") (pin "1") (pinfunction "1_1") (pintype "input"))
      (node (ref "C4") (pin "2") (pinfunction "2_2") (pintype "input"))
      (node (ref "C40") (pin "2") (pinfunction "2_2") (pintype "unspecified"))
      (node (ref "C47") (pin "2") (pinfunction "2_2") (pintype "input"))
      (node (ref "C53") (pin "2") (pinfunction "2_2") (pintype "input"))
      (node (ref "C55") (pin "1") (pinfunction "1_1") (pintype "unspecified"))
      (node (ref "C69") (pin "2") (pinfunction "2_2") (pintype "unspecified"))
      (node (ref "C70") (pin "2") (pinfunction "2_2") (pintype "unspecified"))
      (node (ref "C73") (pin "2") (pinfunction "2_2") (pintype "input"))
      (node (ref "C74") (pin "2") (pinfunction "2_2") (pintype "unspecified"))
      (node (ref "C75") (pin "2") (pinfunction "2_2") (pintype "unspecified"))
      (node (ref "C76") (pin "2") (pinfunction "2_2") (pintype "input"))
      (node (ref "C77") (pin "1") (pinfunction "1_1") (pintype "unspecified"))
      (node (ref "C78") (pin "1") (pinfunction "1_1") (pintype "unspecified"))
      (node (ref "C79") (pin "1") (pinfunction "1_1") (pintype "unspecified"))
      (node (ref "C80") (pin "2") (pinfunction "2_2") (pintype "input"))
      (node (ref "C81") (pin "2") (pinfunction "2_2") (pintype "input"))
      (node (ref "C82") (pin "2") (pinfunction "2_2") (pintype "input"))
      (node (ref "C83") (pin "2") (pinfunction "2_2") (pintype "input"))
      (node (ref "C84") (pin "2") (pinfunction "2_2") (pintype "input"))
      (node (ref "CN1") (pin "1") (pinfunction "1_1") (pintype "input"))
      (node (ref "CN2") (pin "0") (pinfunction "0_0") (pintype "input"))
      (node (ref "CN2") (pin "A1") (pinfunction "GND_A1") (pintype "input"))
      (node (ref "CN2") (pin "A12") (pinfunction "GND_A12") (pintype "input"))
      (node (ref "CN2") (pin "B1") (pinfunction "GND_B1") (pintype "input"))
      (node (ref "CN2") (pin "B12") (pinfunction "GND_B12") (pintype "input"))
      (node (ref "D1") (pin "1") (pinfunction "A_1") (pintype "input"))
      (node (ref "D1") (pin "4") (pinfunction "A_4") (pintype "input"))
      (node (ref "D2") (pin "1") (pinfunction "A_1") (pintype "input"))
      (node (ref "D2") (pin "4") (pinfunction "A_4") (pintype "input"))
      (node (ref "D6") (pin "2") (pinfunction "A_2") (pintype "unspecified"))
      (node (ref "DC1") (pin "2") (pinfunction "2_2") (pintype "input"))
      (node (ref "DEC_TMC") (pin "15") (pinfunction "GND_15") (pintype "input"))
      (node (ref "DEC_TMC") (pin "9") (pinfunction "GND_9") (pintype "input"))
      (node (ref "H1") (pin "1") (pinfunction "1_1") (pintype "input"))
      (node (ref "H1") (pin "2") (pinfunction "2_2") (pintype "input"))
      (node (ref "H2") (pin "7") (pinfunction "7_7") (pintype "input"))
      (node (ref "IN1") (pin "1") (pinfunction "1_1") (pintype "input"))
      (node (ref "JP1") (pin "2") (pinfunction "GND_2") (pintype "input"))
      (node (ref "JP1") (pin "3") (pinfunction "GND_3") (pintype "input"))
      (node (ref "LED2") (pin "1") (pinfunction "K_1") (pintype "input"))
      (node (ref "MX1") (pin "1") (pinfunction "1_1") (pintype "input"))
      (node (ref "R12") (pin "2") (pinfunction "2_2") (pintype "input"))
      (node (ref "R13") (pin "2") (pinfunction "2_2") (pintype "input"))
      (node (ref "R14") (pin "2") (pinfunction "2_2") (pintype "input"))
      (node (ref "R18") (pin "1") (pinfunction "1_1") (pintype "input"))
      (node (ref "R3") (pin "2") (pinfunction "2_2") (pintype "input"))
      (node (ref "R31") (pin "1") (pinfunction "1_1") (pintype "unspecified"))
      (node (ref "R32") (pin "1") (pinfunction "1_1") (pintype "unspecified"))
      (node (ref "R37") (pin "1") (pinfunction "1_1") (pintype "input"))
      (node (ref "R39") (pin "1") (pinfunction "1_1") (pintype "input"))
      (node (ref "R4") (pin "2") (pinfunction "2_2") (pintype "input"))
      (node (ref "R5") (pin "1") (pinfunction "1_1") (pintype "input"))
      (node (ref "R9") (pin "2") (pinfunction "2_2") (pintype "input"))
      (node (ref "RA_TMC") (pin "15") (pinfunction "GND_15") (pintype "input"))
      (node (ref "RA_TMC") (pin "9") (pinfunction "GND_9") (pintype "input"))
      (node (ref "U1") (pin "1") (pinfunction "GND_1") (pintype "input"))
      (node (ref "U1") (pin "33") (pinfunction "GND_33") (pintype "input"))
      (node (ref "U1") (pin "36") (pinfunction "GND_36") (pintype "input"))
      (node (ref "U1") (pin "39") (pinfunction "GND_39") (pintype "input"))
      (node (ref "U1") (pin "45") (pinfunction "GND_45") (pintype "input"))
      (node (ref "U1") (pin "7") (pinfunction "GND_7") (pintype "input"))
      (node (ref "U1") (pin "75") (pinfunction "GND_75") (pintype "input"))
      (node (ref "U11") (pin "1") (pinfunction "A0_1") (pintype "unspecified"))
      (node (ref "U11") (pin "2") (pinfunction "A1_2") (pintype "unspecified"))
      (node (ref "U11") (pin "3") (pinfunction "A2_3") (pintype "unspecified"))
      (node (ref "U13") (pin "1") (pinfunction "1_1") (pintype "unspecified"))
      (node (ref "U2") (pin "1") (pinfunction "GND_1") (pintype "input"))
      (node (ref "U3") (pin "1") (pinfunction "GND_1") (pintype "input"))
      (node (ref "U3") (pin "10") (pinfunction "GND_10") (pintype "input"))
      (node (ref "U3") (pin "12") (pinfunction "GND_12") (pintype "input"))
      (node (ref "U7") (pin "4") (pinfunction "GND_4") (pintype "input"))
      (node (ref "U8") (pin "6") (pinfunction "GND_6") (pintype "input"))
      (node (ref "U9") (pin "4") (pinfunction "GND_4") (pintype "input"))
    )
    (net (code "6") (name "LED") (class "Default")
      (node (ref "R35") (pin "1") (pinfunction "1_1") (pintype "input"))
      (node (ref "U1") (pin "62") (pinfunction "(37)_62") (pintype "bidirectional"))
    )
    (net (code "7") (name "M1_BMA1") (class "Default")
      (node (ref "MOT1") (pin "3") (pinfunction "3_3") (pintype "input"))
      (node (ref "RA_TMC") (pin "12") (pinfunction "1A_12") (pintype "input"))
    )
    (net (code "8") (name "M1_BMA2") (class "Default")
      (node (ref "MOT1") (pin "4") (pinfunction "4_4") (pintype "input"))
      (node (ref "RA_TMC") (pin "11") (pinfunction "1B_11") (pintype "input"))
    )
    (net (code "9") (name "M1_BMB1") (class "Default")
      (node (ref "MOT1") (pin "2") (pinfunction "2_2") (pintype "input"))
      (node (ref "RA_TMC") (pin "13") (pinfunction "2A_13") (pintype "input"))
    )
    (net (code "10") (name "M1_BMB2") (class "Default")
      (node (ref "MOT1") (pin "1") (pinfunction "1_1") (pintype "input"))
      (node (ref "RA_TMC") (pin "14") (pinfunction "2B_14") (pintype "input"))
    )
    (net (code "11") (name "M1_CS") (class "Default")
      (node (ref "RA_TMC") (pin "4") (pinfunction "CS_4") (pintype "input"))
      (node (ref "U1") (pin "55") (pinfunction "SPI_/CS_(10)_55") (pintype "bidirectional"))
    )
    (net (code "12") (name "M1_DIR") (class "Default")
      (node (ref "RA_TMC") (pin "8") (pinfunction "DIR_8") (pintype "input"))
      (node (ref "U1") (pin "51") (pinfunction "I2C_SDA1_(25)_51") (pintype "bidirectional"))
    )
    (net (code "13") (name "M1_ENA") (class "Default")
      (node (ref "BRAKE") (pin "2") (pinfunction "2_2") (pintype "input"))
      (node (ref "RA_TMC") (pin "1") (pinfunction "EN_1") (pintype "input"))
      (node (ref "U1") (pin "53") (pinfunction "I2C_SCL1_(24)_53") (pintype "bidirectional"))
    )
    (net (code "14") (name "M1_ENCA") (class "Default")
      (node (ref "R1") (pin "2") (pinfunction "2_2") (pintype "input"))
      (node (ref "R3") (pin "1") (pinfunction "1_1") (pintype "input"))
      (node (ref "U1") (pin "47") (pinfunction "(2)_47") (pintype "bidirectional"))
    )
    (net (code "15") (name "M1_ENCA_IN") (class "Default")
      (node (ref "H1") (pin "3") (pinfunction "3_3") (pintype "input"))
      (node (ref "R1") (pin "1") (pinfunction "1_1") (pintype "input"))
    )
    (net (code "16") (name "M1_ENCB") (class "Default")
      (node (ref "R2") (pin "2") (pinfunction "2_2") (pintype "input"))
      (node (ref "R4") (pin "1") (pinfunction "1_1") (pintype "input"))
      (node (ref "U1") (pin "41") (pinfunction "CAN-RX_(30)_41") (pintype "bidirectional"))
    )
    (net (code "17") (name "M1_ENCB_IN") (class "Default")
      (node (ref "H1") (pin "5") (pinfunction "5_5") (pintype "input"))
      (node (ref "R2") (pin "1") (pinfunction "1_1") (pintype "input"))
    )
    (net (code "18") (name "M1_ENCX") (class "Default")
      (node (ref "U1") (pin "10") (pinfunction "(4)_10") (pintype "bidirectional"))
    )
    (net (code "19") (name "M1_M4") (class "Default")
      (node (ref "RA_TMC") (pin "6") (pinfunction "M4_6") (pintype "input"))
      (node (ref "U1") (pin "65") (pinfunction "(32)_65") (pintype "bidirectional"))
    )
    (net (code "20") (name "M1_STEP") (class "Default")
      (node (ref "RA_TMC") (pin "7") (pinfunction "STEP_7") (pintype "input"))
      (node (ref "U1") (pin "49") (pinfunction "(22)_49") (pintype "bidirectional"))
    )
    (net (code "21") (name "M2_BMA1") (class "Default")
      (node (ref "DEC_TMC") (pin "12") (pinfunction "1A_12") (pintype "input"))
      (node (ref "MOT2") (pin "3") (pinfunction "3_3") (pintype "input"))
    )
    (net (code "22") (name "M2_BMA2") (class "Default")
      (node (ref "DEC_TMC") (pin "11") (pinfunction "1B_11") (pintype "input"))
      (node (ref "MOT2") (pin "4") (pinfunction "4_4") (pintype "input"))
    )
    (net (code "23") (name "M2_BMB1") (class "Default")
      (node (ref "DEC_TMC") (pin "13") (pinfunction "2A_13") (pintype "input"))
      (node (ref "MOT2") (pin "2") (pinfunction "2_2") (pintype "input"))
    )
    (net (code "24") (name "M2_BMB2") (class "Default")
      (node (ref "DEC_TMC") (pin "14") (pinfunction "2B_14") (pintype "input"))
      (node (ref "MOT2") (pin "1") (pinfunction "1_1") (pintype "input"))
    )
    (net (code "25") (name "M2_CS") (class "Default")
      (node (ref "DEC_TMC") (pin "4") (pinfunction "CS_4") (pintype "input"))
      (node (ref "U1") (pin "46") (pinfunction "(43)_46") (pintype "bidirectional"))
    )
    (net (code "26") (name "M2_DIR") (class "Default")
      (node (ref "DEC_TMC") (pin "8") (pinfunction "DIR_8") (pintype "input"))
      (node (ref "U1") (pin "42") (pinfunction "(41)_42") (pintype "bidirectional"))
    )
    (net (code "27") (name "M2_ENA") (class "Default")
      (node (ref "DEC_TMC") (pin "1") (pinfunction "EN_1") (pintype "input"))
      (node (ref "U1") (pin "44") (pinfunction "(42)_44") (pintype "bidirectional"))
    )
    (net (code "28") (name "M2_ENCA") (class "Default")
      (node (ref "R10") (pin "2") (pinfunction "2_2") (pintype "input"))
      (node (ref "R13") (pin "1") (pinfunction "1_1") (pintype "input"))
      (node (ref "U1") (pin "63") (pinfunction "(33)_63") (pintype "bidirectional"))
    )
    (net (code "29") (name "M2_ENCA_IN") (class "Default")
      (node (ref "H1") (pin "4") (pinfunction "4_4") (pintype "input"))
      (node (ref "R10") (pin "1") (pinfunction "1_1") (pintype "input"))
    )
    (net (code "30") (name "M2_ENCB") (class "Default")
      (node (ref "R11") (pin "2") (pinfunction "2_2") (pintype "input"))
      (node (ref "R14") (pin "1") (pinfunction "1_1") (pintype "input"))
      (node (ref "U1") (pin "43") (pinfunction "CAN-TX_(31)_43") (pintype "bidirectional"))
    )
    (net (code "31") (name "M2_ENCB_IN") (class "Default")
      (node (ref "H1") (pin "6") (pinfunction "6_6") (pintype "input"))
      (node (ref "R11") (pin "1") (pinfunction "1_1") (pintype "input"))
    )
    (net (code "32") (name "M2_ENCX") (class "Default")
      (node (ref "U1") (pin "32") (pinfunction "(3)_32") (pintype "bidirectional"))
    )
    (net (code "33") (name "M2_M4") (class "Default")
      (node (ref "DEC_TMC") (pin "6") (pinfunction "M4_6") (pintype "input"))
      (node (ref "U1") (pin "67") (pinfunction "(26)_67") (pintype "bidirectional"))
    )
    (net (code "34") (name "M2_STEP") (class "Default")
      (node (ref "DEC_TMC") (pin "7") (pinfunction "STEP_7") (pintype "input"))
      (node (ref "U1") (pin "40") (pinfunction "(40)_40") (pintype "bidirectional"))
    )
    (net (code "35") (name "MISO") (class "Default")
      (node (ref "DEC_TMC") (pin "5") (pinfunction "SDO_5") (pintype "input"))
      (node (ref "RA_TMC") (pin "5") (pinfunction "SDO_5") (pintype "input"))
      (node (ref "U1") (pin "61") (pinfunction "SPI_SDI_(12)_61") (pintype "bidirectional"))
    )
    (net (code "36") (name "MOSI") (class "Default")
      (node (ref "DEC_TMC") (pin "2") (pinfunction "SDI_2") (pintype "input"))
      (node (ref "RA_TMC") (pin "2") (pinfunction "SDI_2") (pintype "input"))
      (node (ref "U1") (pin "59") (pinfunction "SPI_SDO_(11)_59") (pintype "bidirectional"))
    )
    (net (code "37") (name "Net-(CN2-CC1)") (class "Default")
      (node (ref "CN2") (pin "A5") (pinfunction "CC1_A5") (pintype "input"))
      (node (ref "R9") (pin "1") (pinfunction "1_1") (pintype "input"))
    )
    (net (code "38") (name "Net-(CN2-CC2)") (class "Default")
      (node (ref "CN2") (pin "B5") (pinfunction "CC2_B5") (pintype "input"))
      (node (ref "R5") (pin "2") (pinfunction "2_2") (pintype "input"))
    )
    (net (code "39") (name "Net-(D3-K)") (class "Default")
      (node (ref "D3") (pin "1") (pinfunction "K_1") (pintype "input"))
      (node (ref "R17") (pin "1") (pinfunction "1_1") (pintype "input"))
    )
    (net (code "40") (name "Net-(DC1-Pad1)") (class "Default")
      (node (ref "DC1") (pin "1") (pinfunction "1_1") (pintype "input"))
      (node (ref "IN1") (pin "2") (pinfunction "2_2") (pintype "input"))
      (node (ref "PS1") (pin "4") (pinfunction "On_4") (pintype "input"))
      (node (ref "U8") (pin "1") (pinfunction "IN_1") (pintype "input"))
      (node (ref "U8") (pin "2") (pinfunction "IN_2") (pintype "input"))
      (node (ref "U8") (pin "3") (pinfunction "IN_3") (pintype "input"))
    )
    (net (code "41") (name "Net-(JP1-SIG)") (class "Default")
      (node (ref "JP1") (pin "1") (pinfunction "SIG_1") (pintype "input"))
      (node (ref "L1") (pin "2") (pinfunction "2_2") (pintype "input"))
      (node (ref "U3") (pin "11") (pinfunction "RF_IN_11") (pintype "input"))
    )
    (net (code "42") (name "Net-(LED1-C)") (class "Default")
      (node (ref "LED1") (pin "2") (pinfunction "C_2") (pintype "input"))
      (node (ref "R12") (pin "1") (pinfunction "1_1") (pintype "input"))
    )
    (net (code "43") (name "Net-(LED2-A)") (class "Default")
      (node (ref "LED2") (pin "2") (pinfunction "A_2") (pintype "input"))
      (node (ref "R35") (pin "2") (pinfunction "2_2") (pintype "input"))
    )
    (net (code "44") (name "Net-(PS1-Comm)") (class "Default")
      (node (ref "PS1") (pin "5") (pinfunction "Comm_5") (pintype "input"))
      (node (ref "R18") (pin "2") (pinfunction "2_2") (pintype "input"))
      (node (ref "U8") (pin "4") (pinfunction "EN_4") (pintype "input"))
    )
    (net (code "45") (name "Net-(PS1-Meca-Pad1)") (class "Default")
      (node (ref "PS1") (pin "1") (pinfunction "Meca_1") (pintype "input"))
      (node (ref "PS1") (pin "2") (pinfunction "Meca_2") (pintype "input"))
    )
    (net (code "46") (name "Net-(U1-RX1_(0))") (class "Default")
      (node (ref "R8") (pin "1") (pinfunction "1_1") (pintype "input"))
      (node (ref "U1") (pin "19") (pinfunction "RX1_(0)_19") (pintype "bidirectional"))
    )
    (net (code "47") (name "Net-(U1-TX1_(1))") (class "Default")
      (node (ref "R7") (pin "1") (pinfunction "1_1") (pintype "input"))
      (node (ref "U1") (pin "17") (pinfunction "TX1_(1)_17") (pintype "bidirectional"))
    )
    (net (code "48") (name "Net-(U3-VCC_RF)") (class "Default")
      (node (ref "L1") (pin "1") (pinfunction "1_1") (pintype "input"))
      (node (ref "U3") (pin "14") (pinfunction "VCC_RF_14") (pintype "input"))
    )
    (net (code "49") (name "Net-(U7-BST)") (class "Default")
      (node (ref "C13") (pin "1") (pinfunction "1_1") (pintype "input"))
      (node (ref "U7") (pin "6") (pinfunction "BST_6") (pintype "input"))
    )
    (net (code "50") (name "Net-(U7-SW)") (class "Default")
      (node (ref "C13") (pin "2") (pinfunction "2_2") (pintype "input"))
      (node (ref "L2") (pin "1") (pinfunction "1_1") (pintype "input"))
      (node (ref "U7") (pin "5") (pinfunction "SW_5") (pintype "input"))
    )
    (net (code "51") (name "Net-(U8-DV{slash}DT)") (class "Default")
      (node (ref "C33") (pin "1") (pinfunction "1_1") (pintype "input"))
      (node (ref "U8") (pin "12") (pinfunction "DV/DT_12") (pintype "input"))
    )
    (net (code "52") (name "Net-(U8-ILIM)") (class "Default")
      (node (ref "R31") (pin "2") (pinfunction "2_2") (pintype "unspecified"))
      (node (ref "U8") (pin "13") (pinfunction "ILIM_13") (pintype "input"))
    )
    (net (code "53") (name "Net-(U8-VLIM)") (class "Default")
      (node (ref "R32") (pin "2") (pinfunction "2_2") (pintype "unspecified"))
      (node (ref "U8") (pin "14") (pinfunction "VLIM_14") (pintype "input"))
    )
    (net (code "54") (name "Net-(U8-VREG)") (class "Default")
      (node (ref "C30") (pin "2") (pinfunction "2_2") (pintype "input"))
      (node (ref "U8") (pin "7") (pinfunction "VREG_7") (pintype "input"))
    )
    (net (code "55") (name "Net-(U9-BST)") (class "Default")
      (node (ref "C37") (pin "1") (pinfunction "1_1") (pintype "input"))
      (node (ref "U9") (pin "6") (pinfunction "BST_6") (pintype "input"))
    )
    (net (code "56") (name "Net-(U9-SW)") (class "Default")
      (node (ref "C37") (pin "2") (pinfunction "2_2") (pintype "input"))
      (node (ref "L3") (pin "1") (pinfunction "1_1") (pintype "input"))
      (node (ref "U9") (pin "5") (pinfunction "SW_5") (pintype "input"))
    )
    (net (code "57") (name "Net-(U11-VDD)") (class "Default")
      (node (ref "C84") (pin "1") (pinfunction "1_1") (pintype "input"))
      (node (ref "FRAM") (pin "1") (pinfunction "1_1") (pintype "input"))
      (node (ref "R40") (pin "1") (pinfunction "1_1") (pintype "input"))
      (node (ref "R41") (pin "2") (pinfunction "2_2") (pintype "input"))
      (node (ref "U11") (pin "8") (pinfunction "VDD_8") (pintype "unspecified"))
    )
    (net (code "58") (name "PPS") (class "Default")
      (node (ref "U1") (pin "18") (pinfunction "(5)_18") (pintype "bidirectional"))
      (node (ref "U3") (pin "4") (pinfunction "1PPS_4") (pintype "input"))
    )
    (net (code "59") (name "PRG_ESP") (class "Default")
      (node (ref "H2") (pin "3") (pinfunction "3_3") (pintype "input"))
      (node (ref "U1") (pin "60") (pinfunction "(36)_60") (pintype "bidirectional"))
      (node (ref "U2") (pin "3") (pinfunction "IO0_3") (pintype "input"))
    )
    (net (code "60") (name "RST_ESP") (class "Default")
      (node (ref "H2") (pin "4") (pinfunction "4_4") (pintype "input"))
      (node (ref "U1") (pin "58") (pinfunction "(23)_58") (pintype "bidirectional"))
      (node (ref "U2") (pin "7") (pinfunction "RST_7") (pintype "input"))
    )
    (net (code "61") (name "RX_DEBUG") (class "Default")
      (node (ref "H2") (pin "8") (pinfunction "8_8") (pintype "input"))
      (node (ref "U1") (pin "56") (pinfunction "RX4_(7)_56") (pintype "bidirectional"))
      (node (ref "U2") (pin "5") (pinfunction "TXD_5") (pintype "input"))
    )
    (net (code "62") (name "RX_GPS") (class "Default")
      (node (ref "U1") (pin "20") (pinfunction "RX2_(16)_20") (pintype "bidirectional"))
      (node (ref "U3") (pin "2") (pinfunction "TXD_2") (pintype "input"))
    )
    (net (code "63") (name "RX_REMOTE") (class "Default")
      (node (ref "CN1") (pin "2") (pinfunction "2_2") (pintype "input"))
      (node (ref "D2") (pin "3") (pinfunction "AC_3") (pintype "input"))
      (node (ref "R8") (pin "2") (pinfunction "2_2") (pintype "input"))
    )
    (net (code "64") (name "SCK") (class "Default")
      (node (ref "DEC_TMC") (pin "3") (pinfunction "SCK_3") (pintype "input"))
      (node (ref "RA_TMC") (pin "3") (pinfunction "SCK_3") (pintype "input"))
      (node (ref "U1") (pin "57") (pinfunction "SPI_SCK_(13)_57") (pintype "bidirectional"))
    )
    (net (code "65") (name "SCL") (class "Default")
      (node (ref "R41") (pin "1") (pinfunction "1_1") (pintype "input"))
      (node (ref "U1") (pin "14") (pinfunction "I2C_SCL_(19)_14") (pintype "bidirectional"))
      (node (ref "U11") (pin "6") (pinfunction "SCL_6") (pintype "unspecified"))
    )
    (net (code "66") (name "SCLG") (class "Default")
      (node (ref "U3") (pin "17") (pinfunction "SCL_17") (pintype "input"))
    )
    (net (code "67") (name "SDA") (class "Default")
      (node (ref "R40") (pin "2") (pinfunction "2_2") (pintype "input"))
      (node (ref "U1") (pin "12") (pinfunction "I2C_SDA_(18)_12") (pintype "bidirectional"))
      (node (ref "U11") (pin "5") (pinfunction "SDA_5") (pintype "unspecified"))
    )
    (net (code "68") (name "SDAG") (class "Default")
      (node (ref "U3") (pin "16") (pinfunction "SDA_16") (pintype "input"))
    )
    (net (code "69") (name "TX_DEBUG") (class "Default")
      (node (ref "H2") (pin "1") (pinfunction "1_1") (pintype "input"))
      (node (ref "U1") (pin "54") (pinfunction "TX4_(8)_54") (pintype "bidirectional"))
      (node (ref "U2") (pin "4") (pinfunction "RXD_4") (pintype "input"))
    )
    (net (code "70") (name "TX_GPS") (class "Default")
      (node (ref "U1") (pin "22") (pinfunction "TX2_(17)_22") (pintype "bidirectional"))
      (node (ref "U3") (pin "3") (pinfunction "RXD_3") (pintype "input"))
    )
    (net (code "71") (name "TX_REMOTE") (class "Default")
      (node (ref "CN1") (pin "3") (pinfunction "3_3") (pintype "input"))
      (node (ref "D2") (pin "6") (pinfunction "AC_6") (pintype "input"))
      (node (ref "R6") (pin "2") (pinfunction "2_2") (pintype "input"))
      (node (ref "R7") (pin "2") (pinfunction "2_2") (pintype "input"))
    )
    (net (code "72") (name "VBAT") (class "Default")
      (node (ref "B1") (pin "1") (pinfunction "1_1") (pintype "input"))
      (node (ref "R17") (pin "2") (pinfunction "2_2") (pintype "input"))
      (node (ref "U1") (pin "72") (pinfunction "RTC_3V_72") (pintype "bidirectional"))
      (node (ref "U3") (pin "6") (pinfunction "VBAT_6") (pintype "input"))
    )
    (net (code "73") (name "VCC") (class "Default")
      (node (ref "BRAKE") (pin "3") (pinfunction "3_3") (pintype "input"))
      (node (ref "C17") (pin "2") (pinfunction "2_2") (pintype "input"))
      (node (ref "C18") (pin "2") (pinfunction "2_2") (pintype "input"))
      (node (ref "C19") (pin "2") (pinfunction "2_2") (pintype "input"))
      (node (ref "C36") (pin "2") (pinfunction "2_2") (pintype "input"))
      (node (ref "C38") (pin "2") (pinfunction "2_2") (pintype "input"))
      (node (ref "C39") (pin "2") (pinfunction "2_2") (pintype "input"))
      (node (ref "C47") (pin "1") (pinfunction "1_1") (pintype "input"))
      (node (ref "C69") (pin "1") (pinfunction "1_1") (pintype "unspecified"))
      (node (ref "C70") (pin "1") (pinfunction "1_1") (pintype "unspecified"))
      (node (ref "C73") (pin "1") (pinfunction "1_1") (pintype "input"))
      (node (ref "C74") (pin "1") (pinfunction "1_1") (pintype "unspecified"))
      (node (ref "C75") (pin "1") (pinfunction "1_1") (pintype "unspecified"))
      (node (ref "C78") (pin "2") (pinfunction "2_2") (pintype "unspecified"))
      (node (ref "C79") (pin "2") (pinfunction "2_2") (pintype "unspecified"))
      (node (ref "C80") (pin "1") (pinfunction "1_1") (pintype "input"))
      (node (ref "C81") (pin "1") (pinfunction "1_1") (pintype "input"))
      (node (ref "C82") (pin "1") (pinfunction "1_1") (pintype "input"))
      (node (ref "C83") (pin "1") (pinfunction "1_1") (pintype "input"))
      (node (ref "D6") (pin "1") (pinfunction "K_1") (pintype "unspecified"))
      (node (ref "DEC_TMC") (pin "16") (pinfunction "VMOT_16") (pintype "input"))
      (node (ref "RA_TMC") (pin "16") (pinfunction "VMOT_16") (pintype "input"))
      (node (ref "U7") (pin "2") (pinfunction "EN_2") (pintype "input"))
      (node (ref "U7") (pin "3") (pinfunction "VIN_3") (pintype "input"))
      (node (ref "U8") (pin "15") (pinfunction "OUT_15") (pintype "input"))
      (node (ref "U8") (pin "16") (pinfunction "OUT_16") (pintype "input"))
      (node (ref "U8") (pin "17") (pinfunction "OUT_17") (pintype "input"))
      (node (ref "U9") (pin "2") (pinfunction "EN_2") (pintype "input"))
      (node (ref "U9") (pin "3") (pinfunction "VIN_3") (pintype "input"))
    )
    (net (code "74") (name "VUSB_IN") (class "Default")
      (node (ref "CN2") (pin "A4") (pinfunction "VBUS_A4") (pintype "input"))
      (node (ref "CN2") (pin "A9") (pinfunction "VBUS_A9") (pintype "input"))
      (node (ref "CN2") (pin "B4") (pinfunction "VBUS_B4") (pintype "input"))
      (node (ref "CN2") (pin "B9") (pinfunction "VBUS_B9") (pintype "input"))
      (node (ref "D1") (pin "2") (pinfunction "C_2") (pintype "input"))
      (node (ref "D1") (pin "5") (pinfunction "C_5") (pintype "input"))
      (node (ref "U1") (pin "9") (pinfunction "USB_VIN_9") (pintype "input"))
      (node (ref "U13") (pin "3") (pinfunction "3_3") (pintype "unspecified"))
    )
    (net (code "75") (name "unconnected-(CN1-Pad5)") (class "Default")
      (node (ref "CN1") (pin "5") (pinfunction "5_5") (pintype "input+no_connect"))
    )
    (net (code "76") (name "unconnected-(CN2-RX1+-PadB11)") (class "Default")
      (node (ref "CN2") (pin "B11") (pinfunction "RX1+_B11") (pintype "input+no_connect"))
    )
    (net (code "77") (name "unconnected-(CN2-RX1--PadB10)") (class "Default")
      (node (ref "CN2") (pin "B10") (pinfunction "RX1-_B10") (pintype "input+no_connect"))
    )
    (net (code "78") (name "unconnected-(CN2-RX2+-PadA11)") (class "Default")
      (node (ref "CN2") (pin "A11") (pinfunction "RX2+_A11") (pintype "input+no_connect"))
    )
    (net (code "79") (name "unconnected-(CN2-RX2--PadA10)") (class "Default")
      (node (ref "CN2") (pin "A10") (pinfunction "RX2-_A10") (pintype "input+no_connect"))
    )
    (net (code "80") (name "unconnected-(CN2-SBU1-PadA8)") (class "Default")
      (node (ref "CN2") (pin "A8") (pinfunction "SBU1_A8") (pintype "input+no_connect"))
    )
    (net (code "81") (name "unconnected-(CN2-SBU2-PadB8)") (class "Default")
      (node (ref "CN2") (pin "B8") (pinfunction "SBU2_B8") (pintype "input+no_connect"))
    )
    (net (code "82") (name "unconnected-(CN2-TX1+-PadA2)") (class "Default")
      (node (ref "CN2") (pin "A2") (pinfunction "TX1+_A2") (pintype "input+no_connect"))
    )
    (net (code "83") (name "unconnected-(CN2-TX1--PadA3)") (class "Default")
      (node (ref "CN2") (pin "A3") (pinfunction "TX1-_A3") (pintype "input+no_connect"))
    )
    (net (code "84") (name "unconnected-(CN2-TX2+-PadB2)") (class "Default")
      (node (ref "CN2") (pin "B2") (pinfunction "TX2+_B2") (pintype "input+no_connect"))
    )
    (net (code "85") (name "unconnected-(CN2-TX2--PadB3)") (class "Default")
      (node (ref "CN2") (pin "B3") (pinfunction "TX2-_B3") (pintype "input+no_connect"))
    )
    (net (code "86") (name "unconnected-(DC1-Pad3)") (class "Default")
      (node (ref "DC1") (pin "3") (pinfunction "3_3") (pintype "input+no_connect"))
    )
    (net (code "87") (name "unconnected-(H2-Pad5)") (class "Default")
      (node (ref "H2") (pin "5") (pinfunction "5_5") (pintype "input+no_connect"))
    )
    (net (code "88") (name "unconnected-(H2-Pad6)") (class "Default")
      (node (ref "H2") (pin "6") (pinfunction "6_6") (pintype "input+no_connect"))
    )
    (net (code "89") (name "unconnected-(PS1-On-Pad6)") (class "Default")
      (node (ref "PS1") (pin "6") (pinfunction "On_6") (pintype "input+no_connect"))
    )
    (net (code "90") (name "unconnected-(R42-Pad1)") (class "Default")
      (node (ref "R42") (pin "1") (pinfunction "1_1") (pintype "unspecified"))
    )
    (net (code "91") (name "unconnected-(R42-Pad2)") (class "Default")
      (node (ref "R42") (pin "2") (pinfunction "2_2") (pintype "unspecified"))
    )
    (net (code "92") (name "unconnected-(U1-(6)-Pad71)") (class "Default")
      (node (ref "U1") (pin "71") (pinfunction "(6)_71") (pintype "bidirectional+no_connect"))
    )
    (net (code "93") (name "unconnected-(U1-(9)-Pad69)") (class "Default")
      (node (ref "U1") (pin "69") (pinfunction "(9)_69") (pintype "bidirectional+no_connect"))
    )
    (net (code "94") (name "unconnected-(U1-(27)-Pad8)") (class "Default")
      (node (ref "U1") (pin "8") (pinfunction "(27)_8") (pintype "bidirectional+no_connect"))
    )
    (net (code "95") (name "unconnected-(U1-(28)-Pad4)") (class "Default")
      (node (ref "U1") (pin "4") (pinfunction "(28)_4") (pintype "bidirectional+no_connect"))
    )
    (net (code "96") (name "unconnected-(U1-(29)-Pad16)") (class "Default")
      (node (ref "U1") (pin "16") (pinfunction "(29)_16") (pintype "bidirectional+no_connect"))
    )
    (net (code "97") (name "unconnected-(U1-(34)-Pad66)") (class "Default")
      (node (ref "U1") (pin "66") (pinfunction "(34)_66") (pintype "bidirectional+no_connect"))
    )
    (net (code "98") (name "unconnected-(U1-(35)-Pad64)") (class "Default")
      (node (ref "U1") (pin "64") (pinfunction "(35)_64") (pintype "bidirectional+no_connect"))
    )
    (net (code "99") (name "unconnected-(U1-(38)-Pad68)") (class "Default")
      (node (ref "U1") (pin "68") (pinfunction "(38)_68") (pintype "bidirectional+no_connect"))
    )
    (net (code "100") (name "unconnected-(U1-(39)-Pad70)") (class "Default")
      (node (ref "U1") (pin "70") (pinfunction "(39)_70") (pintype "bidirectional+no_connect"))
    )
    (net (code "101") (name "unconnected-(U1-(44)-Pad48)") (class "Default")
      (node (ref "U1") (pin "48") (pinfunction "(44)_48") (pintype "bidirectional+no_connect"))
    )
    (net (code "102") (name "unconnected-(U1-(45)-Pad73)") (class "Default")
      (node (ref "U1") (pin "73") (pinfunction "(45)_73") (pintype "bidirectional+no_connect"))
    )
    (net (code "103") (name "unconnected-(U1-(X)-Pad13)") (class "Default")
      (node (ref "U1") (pin "13") (pinfunction "(X)_13") (pintype "input+no_connect"))
    )
    (net (code "104") (name "unconnected-(U1-(X)-Pad15)") (class "Default")
      (node (ref "U1") (pin "15") (pinfunction "(X)_15") (pintype "input+no_connect"))
    )
    (net (code "105") (name "unconnected-(U1-(X)-Pad21)") (class "Default")
      (node (ref "U1") (pin "21") (pinfunction "(X)_21") (pintype "input+no_connect"))
    )
    (net (code "106") (name "unconnected-(U1-(X)-Pad23)") (class "Default")
      (node (ref "U1") (pin "23") (pinfunction "(X)_23") (pintype "input+no_connect"))
    )
    (net (code "107") (name "unconnected-(U1-(X)-Pad35)") (class "Default")
      (node (ref "U1") (pin "35") (pinfunction "(X)_35") (pintype "input+no_connect"))
    )
    (net (code "108") (name "unconnected-(U1-(X)-Pad37)") (class "Default")
      (node (ref "U1") (pin "37") (pinfunction "(X)_37") (pintype "input+no_connect"))
    )
    (net (code "109") (name "unconnected-(U1-ON{slash}OFF-Pad6)") (class "Default")
      (node (ref "U1") (pin "6") (pinfunction "ON/OFF_6") (pintype "input+no_connect"))
    )
    (net (code "110") (name "unconnected-(U1-RX3_(15)-Pad38)") (class "Default")
      (node (ref "U1") (pin "38") (pinfunction "RX3_(15)_38") (pintype "bidirectional+no_connect"))
    )
    (net (code "111") (name "unconnected-(U1-RX5(21)-Pad50)") (class "Default")
      (node (ref "U1") (pin "50") (pinfunction "RX5(21)_50") (pintype "bidirectional+no_connect"))
    )
    (net (code "112") (name "unconnected-(U1-TX3_(14)-Pad34)") (class "Default")
      (node (ref "U1") (pin "34") (pinfunction "TX3_(14)_34") (pintype "bidirectional+no_connect"))
    )
    (net (code "113") (name "unconnected-(U1-TX5(20)-Pad52)") (class "Default")
      (node (ref "U1") (pin "52") (pinfunction "TX5(20)_52") (pintype "bidirectional+no_connect"))
    )
    (net (code "114") (name "unconnected-(U1-{slash}Program-Pad11)") (class "Default")
      (node (ref "U1") (pin "11") (pinfunction "/Program_11") (pintype "input+no_connect"))
    )
    (net (code "115") (name "unconnected-(U2-EN-Pad6)") (class "Default")
      (node (ref "U2") (pin "6") (pinfunction "EN_6") (pintype "input+no_connect"))
    )
    (net (code "116") (name "unconnected-(U2-IO2-Pad2)") (class "Default")
      (node (ref "U2") (pin "2") (pinfunction "IO2_2") (pintype "input+no_connect"))
    )
    (net (code "117") (name "unconnected-(U3-NC-Pad7)") (class "Default")
      (node (ref "U3") (pin "7") (pinfunction "NC_7") (pintype "input+no_connect"))
    )
    (net (code "118") (name "unconnected-(U3-NC-Pad13)") (class "Default")
      (node (ref "U3") (pin "13") (pinfunction "NC_13") (pintype "input+no_connect"))
    )
    (net (code "119") (name "unconnected-(U3-NRESET-Pad9)") (class "Default")
      (node (ref "U3") (pin "9") (pinfunction "NRESET_9") (pintype "input+no_connect"))
    )
    (net (code "120") (name "unconnected-(U3-ON{slash}OFF-Pad5)") (class "Default")
      (node (ref "U3") (pin "5") (pinfunction "ON/OFF_5") (pintype "input+no_connect"))
    )
    (net (code "121") (name "unconnected-(U3-Reserved-Pad15)") (class "Default")
      (node (ref "U3") (pin "15") (pinfunction "Reserved_15") (pintype "input+no_connect"))
    )
    (net (code "122") (name "unconnected-(U3-Reserved-Pad18)") (class "Default")
      (node (ref "U3") (pin "18") (pinfunction "Reserved_18") (pintype "input+no_connect"))
    )
    (net (code "123") (name "unconnected-(U8-DISC1-Pad8)") (class "Default")
      (node (ref "U8") (pin "8") (pinfunction "DISC1_8") (pintype "input+no_connect"))
    )
    (net (code "124") (name "unconnected-(U8-DISC2-Pad9)") (class "Default")
      (node (ref "U8") (pin "9") (pinfunction "DISC2_9") (pintype "input+no_connect"))
    )
    (net (code "125") (name "unconnected-(U8-FAULTB-Pad10)") (class "Default")
      (node (ref "U8") (pin "10") (pinfunction "FAULTB_10") (pintype "input+no_connect"))
    )
    (net (code "126") (name "unconnected-(U8-FRS-Pad5)") (class "Default")
      (node (ref "U8") (pin "5") (pinfunction "FRS_5") (pintype "input+no_connect"))
    )
    (net (code "127") (name "unconnected-(U8-IMON-Pad11)") (class "Default")
      (node (ref "U8") (pin "11") (pinfunction "IMON_11") (pintype "input+no_connect"))
    )
    (net (code "128") (name "unconnected-(U8-SRC-Pad18)") (class "Default")
      (node (ref "U8") (pin "18") (pinfunction "SRC_18") (pintype "input+no_connect"))
    )
    (net (code "129") (name "unconnected-(U11-VSS-Pad4)") (class "Default")
      (node (ref "U11") (pin "4") (pinfunction "VSS_4") (pintype "unspecified"))
    )
    (net (code "130") (name "unconnected-(U11-WP-Pad7)") (class "Default")
      (node (ref "U11") (pin "7") (pinfunction "WP_7") (pintype "unspecified+no_connect"))
    )
    (net (code "131") (name "unconnected-(U12-1PPS-Pad4)") (class "Default")
      (node (ref "U12") (pin "4") (pinfunction "1PPS_4") (pintype "input"))
    )
    (net (code "132") (name "unconnected-(U12-GND-Pad1)") (class "Default")
      (node (ref "U12") (pin "1") (pinfunction "GND_1") (pintype "input"))
    )
    (net (code "133") (name "unconnected-(U12-GND-Pad10)") (class "Default")
      (node (ref "U12") (pin "10") (pinfunction "GND_10") (pintype "input"))
    )
    (net (code "134") (name "unconnected-(U12-GND-Pad12)") (class "Default")
      (node (ref "U12") (pin "12") (pinfunction "GND_12") (pintype "input"))
    )
    (net (code "135") (name "unconnected-(U12-NC-Pad7)") (class "Default")
      (node (ref "U12") (pin "7") (pinfunction "NC_7") (pintype "input+no_connect"))
    )
    (net (code "136") (name "unconnected-(U12-NC-Pad13)") (class "Default")
      (node (ref "U12") (pin "13") (pinfunction "NC_13") (pintype "input+no_connect"))
    )
    (net (code "137") (name "unconnected-(U12-NRESET-Pad9)") (class "Default")
      (node (ref "U12") (pin "9") (pinfunction "NRESET_9") (pintype "input+no_connect"))
    )
    (net (code "138") (name "unconnected-(U12-ON{slash}OFF-Pad5)") (class "Default")
      (node (ref "U12") (pin "5") (pinfunction "ON/OFF_5") (pintype "input+no_connect"))
    )
    (net (code "139") (name "unconnected-(U12-RF_IN-Pad11)") (class "Default")
      (node (ref "U12") (pin "11") (pinfunction "RF_IN_11") (pintype "input"))
    )
    (net (code "140") (name "unconnected-(U12-RXD-Pad3)") (class "Default")
      (node (ref "U12") (pin "3") (pinfunction "RXD_3") (pintype "input"))
    )
    (net (code "141") (name "unconnected-(U12-Reserved-Pad15)") (class "Default")
      (node (ref "U12") (pin "15") (pinfunction "Reserved_15") (pintype "input+no_connect"))
    )
    (net (code "142") (name "unconnected-(U12-Reserved-Pad18)") (class "Default")
      (node (ref "U12") (pin "18") (pinfunction "Reserved_18") (pintype "input+no_connect"))
    )
    (net (code "143") (name "unconnected-(U12-SCL-Pad17)") (class "Default")
      (node (ref "U12") (pin "17") (pinfunction "SCL_17") (pintype "input+no_connect"))
    )
    (net (code "144") (name "unconnected-(U12-SDA-Pad16)") (class "Default")
      (node (ref "U12") (pin "16") (pinfunction "SDA_16") (pintype "input+no_connect"))
    )
    (net (code "145") (name "unconnected-(U12-TXD-Pad2)") (class "Default")
      (node (ref "U12") (pin "2") (pinfunction "TXD_2") (pintype "input"))
    )
    (net (code "146") (name "unconnected-(U12-VBAT-Pad6)") (class "Default")
      (node (ref "U12") (pin "6") (pinfunction "VBAT_6") (pintype "input"))
    )
    (net (code "147") (name "unconnected-(U12-VCC-Pad8)") (class "Default")
      (node (ref "U12") (pin "8") (pinfunction "VCC_8") (pintype "input"))
    )
    (net (code "148") (name "unconnected-(U12-VCC_RF-Pad14)") (class "Default")
      (node (ref "U12") (pin "14") (pinfunction "VCC_RF_14") (pintype "input"))
    )
  )
)
